# Guitutar_LEDS.net
KiCad netlist of a schematic drawn in EAGLE
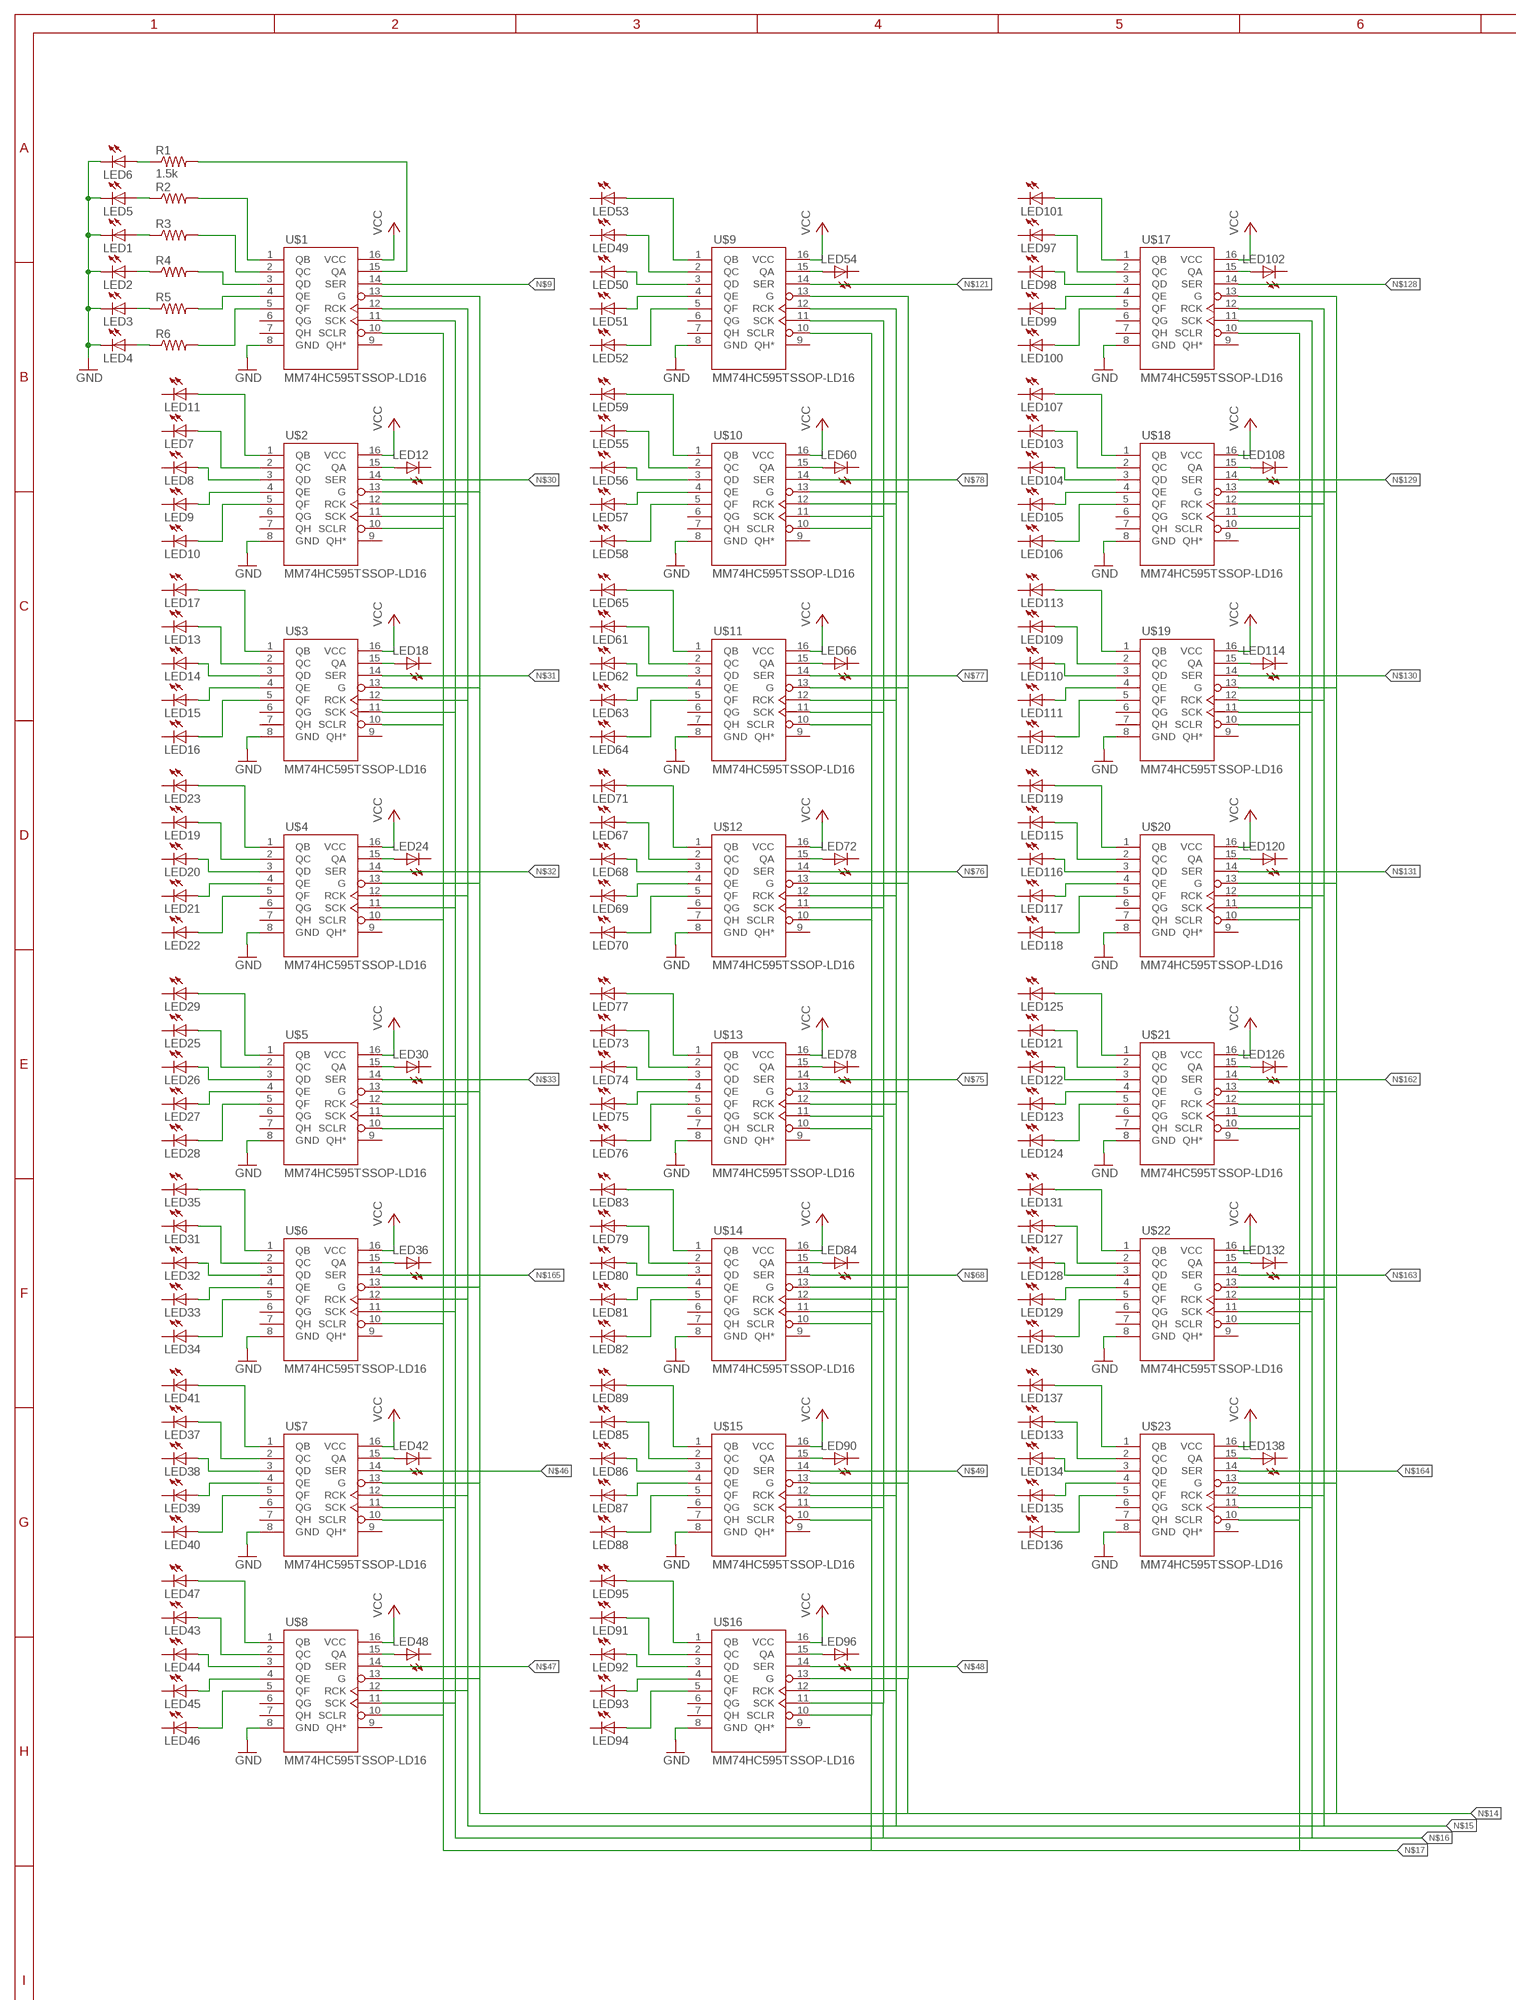
[diagram p0: schematic, sheet 1, part 1 of 2]
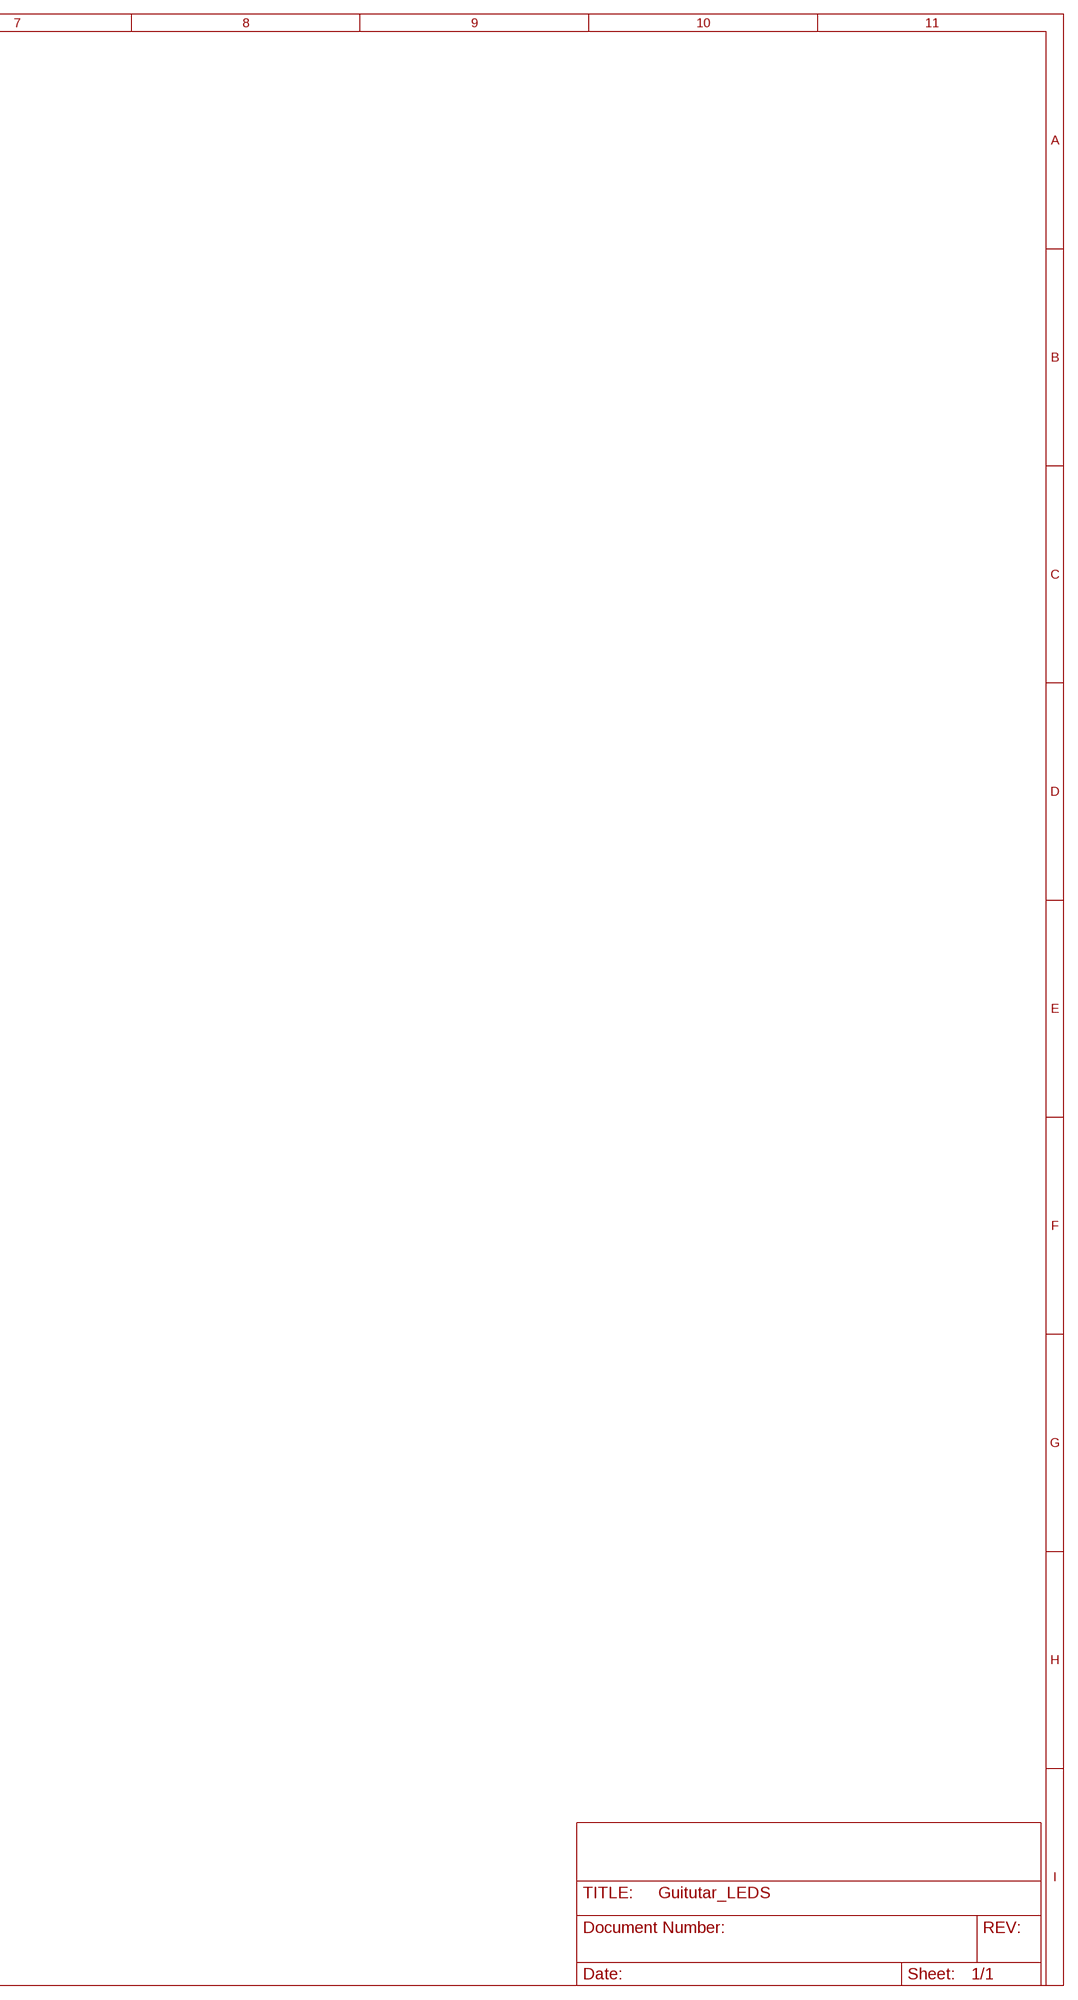
[diagram p1: schematic, sheet 1, part 2 of 2]

(export (version "E")
  (design (tool "Eeschema 10.0.6"))
  (components
    (comp (ref "LED1")
      (value "LEDSMT1206")
      (footprint "eagle-import:1206")
      (libsource (lib "eagle-import") (part "LEDSMT1206"))
    )
    (comp (ref "LED2")
      (value "LEDSMT1206")
      (footprint "eagle-import:1206")
      (libsource (lib "eagle-import") (part "LEDSMT1206"))
    )
    (comp (ref "LED3")
      (value "LEDSMT1206")
      (footprint "eagle-import:1206")
      (libsource (lib "eagle-import") (part "LEDSMT1206"))
    )
    (comp (ref "LED4")
      (value "LEDSMT1206")
      (footprint "eagle-import:1206")
      (libsource (lib "eagle-import") (part "LEDSMT1206"))
    )
    (comp (ref "LED5")
      (value "LEDSMT1206")
      (footprint "eagle-import:1206")
      (libsource (lib "eagle-import") (part "LEDSMT1206"))
    )
    (comp (ref "LED6")
      (value "LEDSMT1206")
      (footprint "eagle-import:1206")
      (libsource (lib "eagle-import") (part "LEDSMT1206"))
    )
    (comp (ref "LED7")
      (value "LEDSMT1206")
      (footprint "eagle-import:1206")
      (libsource (lib "eagle-import") (part "LEDSMT1206"))
    )
    (comp (ref "LED8")
      (value "LEDSMT1206")
      (footprint "eagle-import:1206")
      (libsource (lib "eagle-import") (part "LEDSMT1206"))
    )
    (comp (ref "LED9")
      (value "LEDSMT1206")
      (footprint "eagle-import:1206")
      (libsource (lib "eagle-import") (part "LEDSMT1206"))
    )
    (comp (ref "LED10")
      (value "LEDSMT1206")
      (footprint "eagle-import:1206")
      (libsource (lib "eagle-import") (part "LEDSMT1206"))
    )
    (comp (ref "LED11")
      (value "LEDSMT1206")
      (footprint "eagle-import:1206")
      (libsource (lib "eagle-import") (part "LEDSMT1206"))
    )
    (comp (ref "LED12")
      (value "LEDSMT1206")
      (footprint "eagle-import:1206")
      (libsource (lib "eagle-import") (part "LEDSMT1206"))
    )
    (comp (ref "LED13")
      (value "LEDSMT1206")
      (footprint "eagle-import:1206")
      (libsource (lib "eagle-import") (part "LEDSMT1206"))
    )
    (comp (ref "LED14")
      (value "LEDSMT1206")
      (footprint "eagle-import:1206")
      (libsource (lib "eagle-import") (part "LEDSMT1206"))
    )
    (comp (ref "LED15")
      (value "LEDSMT1206")
      (footprint "eagle-import:1206")
      (libsource (lib "eagle-import") (part "LEDSMT1206"))
    )
    (comp (ref "LED16")
      (value "LEDSMT1206")
      (footprint "eagle-import:1206")
      (libsource (lib "eagle-import") (part "LEDSMT1206"))
    )
    (comp (ref "LED17")
      (value "LEDSMT1206")
      (footprint "eagle-import:1206")
      (libsource (lib "eagle-import") (part "LEDSMT1206"))
    )
    (comp (ref "LED18")
      (value "LEDSMT1206")
      (footprint "eagle-import:1206")
      (libsource (lib "eagle-import") (part "LEDSMT1206"))
    )
    (comp (ref "LED19")
      (value "LEDSMT1206")
      (footprint "eagle-import:1206")
      (libsource (lib "eagle-import") (part "LEDSMT1206"))
    )
    (comp (ref "LED20")
      (value "LEDSMT1206")
      (footprint "eagle-import:1206")
      (libsource (lib "eagle-import") (part "LEDSMT1206"))
    )
    (comp (ref "LED21")
      (value "LEDSMT1206")
      (footprint "eagle-import:1206")
      (libsource (lib "eagle-import") (part "LEDSMT1206"))
    )
    (comp (ref "LED22")
      (value "LEDSMT1206")
      (footprint "eagle-import:1206")
      (libsource (lib "eagle-import") (part "LEDSMT1206"))
    )
    (comp (ref "LED23")
      (value "LEDSMT1206")
      (footprint "eagle-import:1206")
      (libsource (lib "eagle-import") (part "LEDSMT1206"))
    )
    (comp (ref "LED24")
      (value "LEDSMT1206")
      (footprint "eagle-import:1206")
      (libsource (lib "eagle-import") (part "LEDSMT1206"))
    )
    (comp (ref "LED25")
      (value "LEDSMT1206")
      (footprint "eagle-import:1206")
      (libsource (lib "eagle-import") (part "LEDSMT1206"))
    )
    (comp (ref "LED26")
      (value "LEDSMT1206")
      (footprint "eagle-import:1206")
      (libsource (lib "eagle-import") (part "LEDSMT1206"))
    )
    (comp (ref "LED27")
      (value "LEDSMT1206")
      (footprint "eagle-import:1206")
      (libsource (lib "eagle-import") (part "LEDSMT1206"))
    )
    (comp (ref "LED28")
      (value "LEDSMT1206")
      (footprint "eagle-import:1206")
      (libsource (lib "eagle-import") (part "LEDSMT1206"))
    )
    (comp (ref "LED29")
      (value "LEDSMT1206")
      (footprint "eagle-import:1206")
      (libsource (lib "eagle-import") (part "LEDSMT1206"))
    )
    (comp (ref "LED30")
      (value "LEDSMT1206")
      (footprint "eagle-import:1206")
      (libsource (lib "eagle-import") (part "LEDSMT1206"))
    )
    (comp (ref "LED31")
      (value "LEDSMT1206")
      (footprint "eagle-import:1206")
      (libsource (lib "eagle-import") (part "LEDSMT1206"))
    )
    (comp (ref "LED32")
      (value "LEDSMT1206")
      (footprint "eagle-import:1206")
      (libsource (lib "eagle-import") (part "LEDSMT1206"))
    )
    (comp (ref "LED33")
      (value "LEDSMT1206")
      (footprint "eagle-import:1206")
      (libsource (lib "eagle-import") (part "LEDSMT1206"))
    )
    (comp (ref "LED34")
      (value "LEDSMT1206")
      (footprint "eagle-import:1206")
      (libsource (lib "eagle-import") (part "LEDSMT1206"))
    )
    (comp (ref "LED35")
      (value "LEDSMT1206")
      (footprint "eagle-import:1206")
      (libsource (lib "eagle-import") (part "LEDSMT1206"))
    )
    (comp (ref "LED36")
      (value "LEDSMT1206")
      (footprint "eagle-import:1206")
      (libsource (lib "eagle-import") (part "LEDSMT1206"))
    )
    (comp (ref "LED37")
      (value "LEDSMT1206")
      (footprint "eagle-import:1206")
      (libsource (lib "eagle-import") (part "LEDSMT1206"))
    )
    (comp (ref "LED38")
      (value "LEDSMT1206")
      (footprint "eagle-import:1206")
      (libsource (lib "eagle-import") (part "LEDSMT1206"))
    )
    (comp (ref "LED39")
      (value "LEDSMT1206")
      (footprint "eagle-import:1206")
      (libsource (lib "eagle-import") (part "LEDSMT1206"))
    )
    (comp (ref "LED40")
      (value "LEDSMT1206")
      (footprint "eagle-import:1206")
      (libsource (lib "eagle-import") (part "LEDSMT1206"))
    )
    (comp (ref "LED41")
      (value "LEDSMT1206")
      (footprint "eagle-import:1206")
      (libsource (lib "eagle-import") (part "LEDSMT1206"))
    )
    (comp (ref "LED42")
      (value "LEDSMT1206")
      (footprint "eagle-import:1206")
      (libsource (lib "eagle-import") (part "LEDSMT1206"))
    )
    (comp (ref "LED43")
      (value "LEDSMT1206")
      (footprint "eagle-import:1206")
      (libsource (lib "eagle-import") (part "LEDSMT1206"))
    )
    (comp (ref "LED44")
      (value "LEDSMT1206")
      (footprint "eagle-import:1206")
      (libsource (lib "eagle-import") (part "LEDSMT1206"))
    )
    (comp (ref "LED45")
      (value "LEDSMT1206")
      (footprint "eagle-import:1206")
      (libsource (lib "eagle-import") (part "LEDSMT1206"))
    )
    (comp (ref "LED46")
      (value "LEDSMT1206")
      (footprint "eagle-import:1206")
      (libsource (lib "eagle-import") (part "LEDSMT1206"))
    )
    (comp (ref "LED47")
      (value "LEDSMT1206")
      (footprint "eagle-import:1206")
      (libsource (lib "eagle-import") (part "LEDSMT1206"))
    )
    (comp (ref "LED48")
      (value "LEDSMT1206")
      (footprint "eagle-import:1206")
      (libsource (lib "eagle-import") (part "LEDSMT1206"))
    )
    (comp (ref "LED49")
      (value "LEDSMT1206")
      (footprint "eagle-import:1206")
      (libsource (lib "eagle-import") (part "LEDSMT1206"))
    )
    (comp (ref "LED50")
      (value "LEDSMT1206")
      (footprint "eagle-import:1206")
      (libsource (lib "eagle-import") (part "LEDSMT1206"))
    )
    (comp (ref "LED51")
      (value "LEDSMT1206")
      (footprint "eagle-import:1206")
      (libsource (lib "eagle-import") (part "LEDSMT1206"))
    )
    (comp (ref "LED52")
      (value "LEDSMT1206")
      (footprint "eagle-import:1206")
      (libsource (lib "eagle-import") (part "LEDSMT1206"))
    )
    (comp (ref "LED53")
      (value "LEDSMT1206")
      (footprint "eagle-import:1206")
      (libsource (lib "eagle-import") (part "LEDSMT1206"))
    )
    (comp (ref "LED54")
      (value "LEDSMT1206")
      (footprint "eagle-import:1206")
      (libsource (lib "eagle-import") (part "LEDSMT1206"))
    )
    (comp (ref "LED55")
      (value "LEDSMT1206")
      (footprint "eagle-import:1206")
      (libsource (lib "eagle-import") (part "LEDSMT1206"))
    )
    (comp (ref "LED56")
      (value "LEDSMT1206")
      (footprint "eagle-import:1206")
      (libsource (lib "eagle-import") (part "LEDSMT1206"))
    )
    (comp (ref "LED57")
      (value "LEDSMT1206")
      (footprint "eagle-import:1206")
      (libsource (lib "eagle-import") (part "LEDSMT1206"))
    )
    (comp (ref "LED58")
      (value "LEDSMT1206")
      (footprint "eagle-import:1206")
      (libsource (lib "eagle-import") (part "LEDSMT1206"))
    )
    (comp (ref "LED59")
      (value "LEDSMT1206")
      (footprint "eagle-import:1206")
      (libsource (lib "eagle-import") (part "LEDSMT1206"))
    )
    (comp (ref "LED60")
      (value "LEDSMT1206")
      (footprint "eagle-import:1206")
      (libsource (lib "eagle-import") (part "LEDSMT1206"))
    )
    (comp (ref "LED61")
      (value "LEDSMT1206")
      (footprint "eagle-import:1206")
      (libsource (lib "eagle-import") (part "LEDSMT1206"))
    )
    (comp (ref "LED62")
      (value "LEDSMT1206")
      (footprint "eagle-import:1206")
      (libsource (lib "eagle-import") (part "LEDSMT1206"))
    )
    (comp (ref "LED63")
      (value "LEDSMT1206")
      (footprint "eagle-import:1206")
      (libsource (lib "eagle-import") (part "LEDSMT1206"))
    )
    (comp (ref "LED64")
      (value "LEDSMT1206")
      (footprint "eagle-import:1206")
      (libsource (lib "eagle-import") (part "LEDSMT1206"))
    )
    (comp (ref "LED65")
      (value "LEDSMT1206")
      (footprint "eagle-import:1206")
      (libsource (lib "eagle-import") (part "LEDSMT1206"))
    )
    (comp (ref "LED66")
      (value "LEDSMT1206")
      (footprint "eagle-import:1206")
      (libsource (lib "eagle-import") (part "LEDSMT1206"))
    )
    (comp (ref "LED67")
      (value "LEDSMT1206")
      (footprint "eagle-import:1206")
      (libsource (lib "eagle-import") (part "LEDSMT1206"))
    )
    (comp (ref "LED68")
      (value "LEDSMT1206")
      (footprint "eagle-import:1206")
      (libsource (lib "eagle-import") (part "LEDSMT1206"))
    )
    (comp (ref "LED69")
      (value "LEDSMT1206")
      (footprint "eagle-import:1206")
      (libsource (lib "eagle-import") (part "LEDSMT1206"))
    )
    (comp (ref "LED70")
      (value "LEDSMT1206")
      (footprint "eagle-import:1206")
      (libsource (lib "eagle-import") (part "LEDSMT1206"))
    )
    (comp (ref "LED71")
      (value "LEDSMT1206")
      (footprint "eagle-import:1206")
      (libsource (lib "eagle-import") (part "LEDSMT1206"))
    )
    (comp (ref "LED72")
      (value "LEDSMT1206")
      (footprint "eagle-import:1206")
      (libsource (lib "eagle-import") (part "LEDSMT1206"))
    )
    (comp (ref "LED73")
      (value "LEDSMT1206")
      (footprint "eagle-import:1206")
      (libsource (lib "eagle-import") (part "LEDSMT1206"))
    )
    (comp (ref "LED74")
      (value "LEDSMT1206")
      (footprint "eagle-import:1206")
      (libsource (lib "eagle-import") (part "LEDSMT1206"))
    )
    (comp (ref "LED75")
      (value "LEDSMT1206")
      (footprint "eagle-import:1206")
      (libsource (lib "eagle-import") (part "LEDSMT1206"))
    )
    (comp (ref "LED76")
      (value "LEDSMT1206")
      (footprint "eagle-import:1206")
      (libsource (lib "eagle-import") (part "LEDSMT1206"))
    )
    (comp (ref "LED77")
      (value "LEDSMT1206")
      (footprint "eagle-import:1206")
      (libsource (lib "eagle-import") (part "LEDSMT1206"))
    )
    (comp (ref "LED78")
      (value "LEDSMT1206")
      (footprint "eagle-import:1206")
      (libsource (lib "eagle-import") (part "LEDSMT1206"))
    )
    (comp (ref "LED79")
      (value "LEDSMT1206")
      (footprint "eagle-import:1206")
      (libsource (lib "eagle-import") (part "LEDSMT1206"))
    )
    (comp (ref "LED80")
      (value "LEDSMT1206")
      (footprint "eagle-import:1206")
      (libsource (lib "eagle-import") (part "LEDSMT1206"))
    )
    (comp (ref "LED81")
      (value "LEDSMT1206")
      (footprint "eagle-import:1206")
      (libsource (lib "eagle-import") (part "LEDSMT1206"))
    )
    (comp (ref "LED82")
      (value "LEDSMT1206")
      (footprint "eagle-import:1206")
      (libsource (lib "eagle-import") (part "LEDSMT1206"))
    )
    (comp (ref "LED83")
      (value "LEDSMT1206")
      (footprint "eagle-import:1206")
      (libsource (lib "eagle-import") (part "LEDSMT1206"))
    )
    (comp (ref "LED84")
      (value "LEDSMT1206")
      (footprint "eagle-import:1206")
      (libsource (lib "eagle-import") (part "LEDSMT1206"))
    )
    (comp (ref "LED85")
      (value "LEDSMT1206")
      (footprint "eagle-import:1206")
      (libsource (lib "eagle-import") (part "LEDSMT1206"))
    )
    (comp (ref "LED86")
      (value "LEDSMT1206")
      (footprint "eagle-import:1206")
      (libsource (lib "eagle-import") (part "LEDSMT1206"))
    )
    (comp (ref "LED87")
      (value "LEDSMT1206")
      (footprint "eagle-import:1206")
      (libsource (lib "eagle-import") (part "LEDSMT1206"))
    )
    (comp (ref "LED88")
      (value "LEDSMT1206")
      (footprint "eagle-import:1206")
      (libsource (lib "eagle-import") (part "LEDSMT1206"))
    )
    (comp (ref "LED89")
      (value "LEDSMT1206")
      (footprint "eagle-import:1206")
      (libsource (lib "eagle-import") (part "LEDSMT1206"))
    )
    (comp (ref "LED90")
      (value "LEDSMT1206")
      (footprint "eagle-import:1206")
      (libsource (lib "eagle-import") (part "LEDSMT1206"))
    )
    (comp (ref "LED91")
      (value "LEDSMT1206")
      (footprint "eagle-import:1206")
      (libsource (lib "eagle-import") (part "LEDSMT1206"))
    )
    (comp (ref "LED92")
      (value "LEDSMT1206")
      (footprint "eagle-import:1206")
      (libsource (lib "eagle-import") (part "LEDSMT1206"))
    )
    (comp (ref "LED93")
      (value "LEDSMT1206")
      (footprint "eagle-import:1206")
      (libsource (lib "eagle-import") (part "LEDSMT1206"))
    )
    (comp (ref "LED94")
      (value "LEDSMT1206")
      (footprint "eagle-import:1206")
      (libsource (lib "eagle-import") (part "LEDSMT1206"))
    )
    (comp (ref "LED95")
      (value "LEDSMT1206")
      (footprint "eagle-import:1206")
      (libsource (lib "eagle-import") (part "LEDSMT1206"))
    )
    (comp (ref "LED96")
      (value "LEDSMT1206")
      (footprint "eagle-import:1206")
      (libsource (lib "eagle-import") (part "LEDSMT1206"))
    )
    (comp (ref "LED97")
      (value "LEDSMT1206")
      (footprint "eagle-import:1206")
      (libsource (lib "eagle-import") (part "LEDSMT1206"))
    )
    (comp (ref "LED98")
      (value "LEDSMT1206")
      (footprint "eagle-import:1206")
      (libsource (lib "eagle-import") (part "LEDSMT1206"))
    )
    (comp (ref "LED99")
      (value "LEDSMT1206")
      (footprint "eagle-import:1206")
      (libsource (lib "eagle-import") (part "LEDSMT1206"))
    )
    (comp (ref "LED100")
      (value "LEDSMT1206")
      (footprint "eagle-import:1206")
      (libsource (lib "eagle-import") (part "LEDSMT1206"))
    )
    (comp (ref "LED101")
      (value "LEDSMT1206")
      (footprint "eagle-import:1206")
      (libsource (lib "eagle-import") (part "LEDSMT1206"))
    )
    (comp (ref "LED102")
      (value "LEDSMT1206")
      (footprint "eagle-import:1206")
      (libsource (lib "eagle-import") (part "LEDSMT1206"))
    )
    (comp (ref "LED103")
      (value "LEDSMT1206")
      (footprint "eagle-import:1206")
      (libsource (lib "eagle-import") (part "LEDSMT1206"))
    )
    (comp (ref "LED104")
      (value "LEDSMT1206")
      (footprint "eagle-import:1206")
      (libsource (lib "eagle-import") (part "LEDSMT1206"))
    )
    (comp (ref "LED105")
      (value "LEDSMT1206")
      (footprint "eagle-import:1206")
      (libsource (lib "eagle-import") (part "LEDSMT1206"))
    )
    (comp (ref "LED106")
      (value "LEDSMT1206")
      (footprint "eagle-import:1206")
      (libsource (lib "eagle-import") (part "LEDSMT1206"))
    )
    (comp (ref "LED107")
      (value "LEDSMT1206")
      (footprint "eagle-import:1206")
      (libsource (lib "eagle-import") (part "LEDSMT1206"))
    )
    (comp (ref "LED108")
      (value "LEDSMT1206")
      (footprint "eagle-import:1206")
      (libsource (lib "eagle-import") (part "LEDSMT1206"))
    )
    (comp (ref "LED109")
      (value "LEDSMT1206")
      (footprint "eagle-import:1206")
      (libsource (lib "eagle-import") (part "LEDSMT1206"))
    )
    (comp (ref "LED110")
      (value "LEDSMT1206")
      (footprint "eagle-import:1206")
      (libsource (lib "eagle-import") (part "LEDSMT1206"))
    )
    (comp (ref "LED111")
      (value "LEDSMT1206")
      (footprint "eagle-import:1206")
      (libsource (lib "eagle-import") (part "LEDSMT1206"))
    )
    (comp (ref "LED112")
      (value "LEDSMT1206")
      (footprint "eagle-import:1206")
      (libsource (lib "eagle-import") (part "LEDSMT1206"))
    )
    (comp (ref "LED113")
      (value "LEDSMT1206")
      (footprint "eagle-import:1206")
      (libsource (lib "eagle-import") (part "LEDSMT1206"))
    )
    (comp (ref "LED114")
      (value "LEDSMT1206")
      (footprint "eagle-import:1206")
      (libsource (lib "eagle-import") (part "LEDSMT1206"))
    )
    (comp (ref "LED115")
      (value "LEDSMT1206")
      (footprint "eagle-import:1206")
      (libsource (lib "eagle-import") (part "LEDSMT1206"))
    )
    (comp (ref "LED116")
      (value "LEDSMT1206")
      (footprint "eagle-import:1206")
      (libsource (lib "eagle-import") (part "LEDSMT1206"))
    )
    (comp (ref "LED117")
      (value "LEDSMT1206")
      (footprint "eagle-import:1206")
      (libsource (lib "eagle-import") (part "LEDSMT1206"))
    )
    (comp (ref "LED118")
      (value "LEDSMT1206")
      (footprint "eagle-import:1206")
      (libsource (lib "eagle-import") (part "LEDSMT1206"))
    )
    (comp (ref "LED119")
      (value "LEDSMT1206")
      (footprint "eagle-import:1206")
      (libsource (lib "eagle-import") (part "LEDSMT1206"))
    )
    (comp (ref "LED120")
      (value "LEDSMT1206")
      (footprint "eagle-import:1206")
      (libsource (lib "eagle-import") (part "LEDSMT1206"))
    )
    (comp (ref "LED121")
      (value "LEDSMT1206")
      (footprint "eagle-import:1206")
      (libsource (lib "eagle-import") (part "LEDSMT1206"))
    )
    (comp (ref "LED122")
      (value "LEDSMT1206")
      (footprint "eagle-import:1206")
      (libsource (lib "eagle-import") (part "LEDSMT1206"))
    )
    (comp (ref "LED123")
      (value "LEDSMT1206")
      (footprint "eagle-import:1206")
      (libsource (lib "eagle-import") (part "LEDSMT1206"))
    )
    (comp (ref "LED124")
      (value "LEDSMT1206")
      (footprint "eagle-import:1206")
      (libsource (lib "eagle-import") (part "LEDSMT1206"))
    )
    (comp (ref "LED125")
      (value "LEDSMT1206")
      (footprint "eagle-import:1206")
      (libsource (lib "eagle-import") (part "LEDSMT1206"))
    )
    (comp (ref "LED126")
      (value "LEDSMT1206")
      (footprint "eagle-import:1206")
      (libsource (lib "eagle-import") (part "LEDSMT1206"))
    )
    (comp (ref "LED127")
      (value "LEDSMT1206")
      (footprint "eagle-import:1206")
      (libsource (lib "eagle-import") (part "LEDSMT1206"))
    )
    (comp (ref "LED128")
      (value "LEDSMT1206")
      (footprint "eagle-import:1206")
      (libsource (lib "eagle-import") (part "LEDSMT1206"))
    )
    (comp (ref "LED129")
      (value "LEDSMT1206")
      (footprint "eagle-import:1206")
      (libsource (lib "eagle-import") (part "LEDSMT1206"))
    )
    (comp (ref "LED130")
      (value "LEDSMT1206")
      (footprint "eagle-import:1206")
      (libsource (lib "eagle-import") (part "LEDSMT1206"))
    )
    (comp (ref "LED131")
      (value "LEDSMT1206")
      (footprint "eagle-import:1206")
      (libsource (lib "eagle-import") (part "LEDSMT1206"))
    )
    (comp (ref "LED132")
      (value "LEDSMT1206")
      (footprint "eagle-import:1206")
      (libsource (lib "eagle-import") (part "LEDSMT1206"))
    )
    (comp (ref "LED133")
      (value "LEDSMT1206")
      (footprint "eagle-import:1206")
      (libsource (lib "eagle-import") (part "LEDSMT1206"))
    )
    (comp (ref "LED134")
      (value "LEDSMT1206")
      (footprint "eagle-import:1206")
      (libsource (lib "eagle-import") (part "LEDSMT1206"))
    )
    (comp (ref "LED135")
      (value "LEDSMT1206")
      (footprint "eagle-import:1206")
      (libsource (lib "eagle-import") (part "LEDSMT1206"))
    )
    (comp (ref "LED136")
      (value "LEDSMT1206")
      (footprint "eagle-import:1206")
      (libsource (lib "eagle-import") (part "LEDSMT1206"))
    )
    (comp (ref "LED137")
      (value "LEDSMT1206")
      (footprint "eagle-import:1206")
      (libsource (lib "eagle-import") (part "LEDSMT1206"))
    )
    (comp (ref "LED138")
      (value "LEDSMT1206")
      (footprint "eagle-import:1206")
      (libsource (lib "eagle-import") (part "LEDSMT1206"))
    )
    (comp (ref "R1")
      (value "1.5k")
      (footprint "eagle-import:R0603")
      (libsource (lib "eagle-import") (part "R-US_R0603"))
    )
    (comp (ref "R2")
      (value "R-US_R0603")
      (footprint "eagle-import:R0603")
      (libsource (lib "eagle-import") (part "R-US_R0603"))
    )
    (comp (ref "R3")
      (value "R-US_R0603")
      (footprint "eagle-import:R0603")
      (libsource (lib "eagle-import") (part "R-US_R0603"))
    )
    (comp (ref "R4")
      (value "R-US_R0603")
      (footprint "eagle-import:R0603")
      (libsource (lib "eagle-import") (part "R-US_R0603"))
    )
    (comp (ref "R5")
      (value "R-US_R0603")
      (footprint "eagle-import:R0603")
      (libsource (lib "eagle-import") (part "R-US_R0603"))
    )
    (comp (ref "R6")
      (value "R-US_R0603")
      (footprint "eagle-import:R0603")
      (libsource (lib "eagle-import") (part "R-US_R0603"))
    )
    (comp (ref "U$1")
      (value "MM74HC595TSSOP-LD16")
      (footprint "eagle-import:MM74HC595MTCXCT-ND")
      (libsource (lib "eagle-import") (part "MM74HC595TSSOP-LD16"))
    )
    (comp (ref "U$2")
      (value "MM74HC595TSSOP-LD16")
      (footprint "eagle-import:MM74HC595MTCXCT-ND")
      (libsource (lib "eagle-import") (part "MM74HC595TSSOP-LD16"))
    )
    (comp (ref "U$3")
      (value "MM74HC595TSSOP-LD16")
      (footprint "eagle-import:MM74HC595MTCXCT-ND")
      (libsource (lib "eagle-import") (part "MM74HC595TSSOP-LD16"))
    )
    (comp (ref "U$4")
      (value "MM74HC595TSSOP-LD16")
      (footprint "eagle-import:MM74HC595MTCXCT-ND")
      (libsource (lib "eagle-import") (part "MM74HC595TSSOP-LD16"))
    )
    (comp (ref "U$5")
      (value "MM74HC595TSSOP-LD16")
      (footprint "eagle-import:MM74HC595MTCXCT-ND")
      (libsource (lib "eagle-import") (part "MM74HC595TSSOP-LD16"))
    )
    (comp (ref "U$6")
      (value "MM74HC595TSSOP-LD16")
      (footprint "eagle-import:MM74HC595MTCXCT-ND")
      (libsource (lib "eagle-import") (part "MM74HC595TSSOP-LD16"))
    )
    (comp (ref "U$7")
      (value "MM74HC595TSSOP-LD16")
      (footprint "eagle-import:MM74HC595MTCXCT-ND")
      (libsource (lib "eagle-import") (part "MM74HC595TSSOP-LD16"))
    )
    (comp (ref "U$8")
      (value "MM74HC595TSSOP-LD16")
      (footprint "eagle-import:MM74HC595MTCXCT-ND")
      (libsource (lib "eagle-import") (part "MM74HC595TSSOP-LD16"))
    )
    (comp (ref "U$9")
      (value "MM74HC595TSSOP-LD16")
      (footprint "eagle-import:MM74HC595MTCXCT-ND")
      (libsource (lib "eagle-import") (part "MM74HC595TSSOP-LD16"))
    )
    (comp (ref "U$10")
      (value "MM74HC595TSSOP-LD16")
      (footprint "eagle-import:MM74HC595MTCXCT-ND")
      (libsource (lib "eagle-import") (part "MM74HC595TSSOP-LD16"))
    )
    (comp (ref "U$11")
      (value "MM74HC595TSSOP-LD16")
      (footprint "eagle-import:MM74HC595MTCXCT-ND")
      (libsource (lib "eagle-import") (part "MM74HC595TSSOP-LD16"))
    )
    (comp (ref "U$12")
      (value "MM74HC595TSSOP-LD16")
      (footprint "eagle-import:MM74HC595MTCXCT-ND")
      (libsource (lib "eagle-import") (part "MM74HC595TSSOP-LD16"))
    )
    (comp (ref "U$13")
      (value "MM74HC595TSSOP-LD16")
      (footprint "eagle-import:MM74HC595MTCXCT-ND")
      (libsource (lib "eagle-import") (part "MM74HC595TSSOP-LD16"))
    )
    (comp (ref "U$14")
      (value "MM74HC595TSSOP-LD16")
      (footprint "eagle-import:MM74HC595MTCXCT-ND")
      (libsource (lib "eagle-import") (part "MM74HC595TSSOP-LD16"))
    )
    (comp (ref "U$15")
      (value "MM74HC595TSSOP-LD16")
      (footprint "eagle-import:MM74HC595MTCXCT-ND")
      (libsource (lib "eagle-import") (part "MM74HC595TSSOP-LD16"))
    )
    (comp (ref "U$16")
      (value "MM74HC595TSSOP-LD16")
      (footprint "eagle-import:MM74HC595MTCXCT-ND")
      (libsource (lib "eagle-import") (part "MM74HC595TSSOP-LD16"))
    )
    (comp (ref "U$17")
      (value "MM74HC595TSSOP-LD16")
      (footprint "eagle-import:MM74HC595MTCXCT-ND")
      (libsource (lib "eagle-import") (part "MM74HC595TSSOP-LD16"))
    )
    (comp (ref "U$18")
      (value "MM74HC595TSSOP-LD16")
      (footprint "eagle-import:MM74HC595MTCXCT-ND")
      (libsource (lib "eagle-import") (part "MM74HC595TSSOP-LD16"))
    )
    (comp (ref "U$19")
      (value "MM74HC595TSSOP-LD16")
      (footprint "eagle-import:MM74HC595MTCXCT-ND")
      (libsource (lib "eagle-import") (part "MM74HC595TSSOP-LD16"))
    )
    (comp (ref "U$20")
      (value "MM74HC595TSSOP-LD16")
      (footprint "eagle-import:MM74HC595MTCXCT-ND")
      (libsource (lib "eagle-import") (part "MM74HC595TSSOP-LD16"))
    )
    (comp (ref "U$21")
      (value "MM74HC595TSSOP-LD16")
      (footprint "eagle-import:MM74HC595MTCXCT-ND")
      (libsource (lib "eagle-import") (part "MM74HC595TSSOP-LD16"))
    )
    (comp (ref "U$22")
      (value "MM74HC595TSSOP-LD16")
      (footprint "eagle-import:MM74HC595MTCXCT-ND")
      (libsource (lib "eagle-import") (part "MM74HC595TSSOP-LD16"))
    )
    (comp (ref "U$23")
      (value "MM74HC595TSSOP-LD16")
      (footprint "eagle-import:MM74HC595MTCXCT-ND")
      (libsource (lib "eagle-import") (part "MM74HC595TSSOP-LD16"))
    )
  )
  (nets
    (net (code "1") (name "GND") (class "Default")
      (node (ref "LED1") (pin "C") (pinfunction "C_C") (pintype "passive"))
      (node (ref "LED2") (pin "C") (pinfunction "C_C") (pintype "passive"))
      (node (ref "LED3") (pin "C") (pinfunction "C_C") (pintype "passive"))
      (node (ref "LED4") (pin "C") (pinfunction "C_C") (pintype "passive"))
      (node (ref "LED5") (pin "C") (pinfunction "C_C") (pintype "passive"))
      (node (ref "LED6") (pin "C") (pinfunction "C_C") (pintype "passive"))
      (node (ref "U$1") (pin "8") (pinfunction "GND_8") (pintype "bidirectional"))
      (node (ref "U$10") (pin "8") (pinfunction "GND_8") (pintype "bidirectional"))
      (node (ref "U$11") (pin "8") (pinfunction "GND_8") (pintype "bidirectional"))
      (node (ref "U$12") (pin "8") (pinfunction "GND_8") (pintype "bidirectional"))
      (node (ref "U$13") (pin "8") (pinfunction "GND_8") (pintype "bidirectional"))
      (node (ref "U$14") (pin "8") (pinfunction "GND_8") (pintype "bidirectional"))
      (node (ref "U$15") (pin "8") (pinfunction "GND_8") (pintype "bidirectional"))
      (node (ref "U$16") (pin "8") (pinfunction "GND_8") (pintype "bidirectional"))
      (node (ref "U$17") (pin "8") (pinfunction "GND_8") (pintype "bidirectional"))
      (node (ref "U$18") (pin "8") (pinfunction "GND_8") (pintype "bidirectional"))
      (node (ref "U$19") (pin "8") (pinfunction "GND_8") (pintype "bidirectional"))
      (node (ref "U$2") (pin "8") (pinfunction "GND_8") (pintype "bidirectional"))
      (node (ref "U$20") (pin "8") (pinfunction "GND_8") (pintype "bidirectional"))
      (node (ref "U$21") (pin "8") (pinfunction "GND_8") (pintype "bidirectional"))
      (node (ref "U$22") (pin "8") (pinfunction "GND_8") (pintype "bidirectional"))
      (node (ref "U$23") (pin "8") (pinfunction "GND_8") (pintype "bidirectional"))
      (node (ref "U$3") (pin "8") (pinfunction "GND_8") (pintype "bidirectional"))
      (node (ref "U$4") (pin "8") (pinfunction "GND_8") (pintype "bidirectional"))
      (node (ref "U$5") (pin "8") (pinfunction "GND_8") (pintype "bidirectional"))
      (node (ref "U$6") (pin "8") (pinfunction "GND_8") (pintype "bidirectional"))
      (node (ref "U$7") (pin "8") (pinfunction "GND_8") (pintype "bidirectional"))
      (node (ref "U$8") (pin "8") (pinfunction "GND_8") (pintype "bidirectional"))
      (node (ref "U$9") (pin "8") (pinfunction "GND_8") (pintype "bidirectional"))
    )
    (net (code "2") (name "N$9") (class "Default")
      (node (ref "U$1") (pin "14") (pinfunction "SER_14") (pintype "bidirectional"))
    )
    (net (code "3") (name "N$14") (class "Default")
      (node (ref "U$1") (pin "13") (pinfunction "G_13") (pintype "bidirectional"))
      (node (ref "U$10") (pin "13") (pinfunction "G_13") (pintype "bidirectional"))
      (node (ref "U$11") (pin "13") (pinfunction "G_13") (pintype "bidirectional"))
      (node (ref "U$12") (pin "13") (pinfunction "G_13") (pintype "bidirectional"))
      (node (ref "U$13") (pin "13") (pinfunction "G_13") (pintype "bidirectional"))
      (node (ref "U$14") (pin "13") (pinfunction "G_13") (pintype "bidirectional"))
      (node (ref "U$15") (pin "13") (pinfunction "G_13") (pintype "bidirectional"))
      (node (ref "U$16") (pin "13") (pinfunction "G_13") (pintype "bidirectional"))
      (node (ref "U$17") (pin "13") (pinfunction "G_13") (pintype "bidirectional"))
      (node (ref "U$18") (pin "13") (pinfunction "G_13") (pintype "bidirectional"))
      (node (ref "U$19") (pin "13") (pinfunction "G_13") (pintype "bidirectional"))
      (node (ref "U$2") (pin "13") (pinfunction "G_13") (pintype "bidirectional"))
      (node (ref "U$20") (pin "13") (pinfunction "G_13") (pintype "bidirectional"))
      (node (ref "U$21") (pin "13") (pinfunction "G_13") (pintype "bidirectional"))
      (node (ref "U$22") (pin "13") (pinfunction "G_13") (pintype "bidirectional"))
      (node (ref "U$23") (pin "13") (pinfunction "G_13") (pintype "bidirectional"))
      (node (ref "U$3") (pin "13") (pinfunction "G_13") (pintype "bidirectional"))
      (node (ref "U$4") (pin "13") (pinfunction "G_13") (pintype "bidirectional"))
      (node (ref "U$5") (pin "13") (pinfunction "G_13") (pintype "bidirectional"))
      (node (ref "U$6") (pin "13") (pinfunction "G_13") (pintype "bidirectional"))
      (node (ref "U$7") (pin "13") (pinfunction "G_13") (pintype "bidirectional"))
      (node (ref "U$8") (pin "13") (pinfunction "G_13") (pintype "bidirectional"))
      (node (ref "U$9") (pin "13") (pinfunction "G_13") (pintype "bidirectional"))
    )
    (net (code "4") (name "N$15") (class "Default")
      (node (ref "U$1") (pin "12") (pinfunction "RCK_12") (pintype "bidirectional"))
      (node (ref "U$10") (pin "12") (pinfunction "RCK_12") (pintype "bidirectional"))
      (node (ref "U$11") (pin "12") (pinfunction "RCK_12") (pintype "bidirectional"))
      (node (ref "U$12") (pin "12") (pinfunction "RCK_12") (pintype "bidirectional"))
      (node (ref "U$13") (pin "12") (pinfunction "RCK_12") (pintype "bidirectional"))
      (node (ref "U$14") (pin "12") (pinfunction "RCK_12") (pintype "bidirectional"))
      (node (ref "U$15") (pin "12") (pinfunction "RCK_12") (pintype "bidirectional"))
      (node (ref "U$16") (pin "12") (pinfunction "RCK_12") (pintype "bidirectional"))
      (node (ref "U$17") (pin "12") (pinfunction "RCK_12") (pintype "bidirectional"))
      (node (ref "U$18") (pin "12") (pinfunction "RCK_12") (pintype "bidirectional"))
      (node (ref "U$19") (pin "12") (pinfunction "RCK_12") (pintype "bidirectional"))
      (node (ref "U$2") (pin "12") (pinfunction "RCK_12") (pintype "bidirectional"))
      (node (ref "U$20") (pin "12") (pinfunction "RCK_12") (pintype "bidirectional"))
      (node (ref "U$21") (pin "12") (pinfunction "RCK_12") (pintype "bidirectional"))
      (node (ref "U$22") (pin "12") (pinfunction "RCK_12") (pintype "bidirectional"))
      (node (ref "U$23") (pin "12") (pinfunction "RCK_12") (pintype "bidirectional"))
      (node (ref "U$3") (pin "12") (pinfunction "RCK_12") (pintype "bidirectional"))
      (node (ref "U$4") (pin "12") (pinfunction "RCK_12") (pintype "bidirectional"))
      (node (ref "U$5") (pin "12") (pinfunction "RCK_12") (pintype "bidirectional"))
      (node (ref "U$6") (pin "12") (pinfunction "RCK_12") (pintype "bidirectional"))
      (node (ref "U$7") (pin "12") (pinfunction "RCK_12") (pintype "bidirectional"))
      (node (ref "U$8") (pin "12") (pinfunction "RCK_12") (pintype "bidirectional"))
      (node (ref "U$9") (pin "12") (pinfunction "RCK_12") (pintype "bidirectional"))
    )
    (net (code "5") (name "N$16") (class "Default")
      (node (ref "U$1") (pin "11") (pinfunction "SCK_11") (pintype "bidirectional"))
      (node (ref "U$10") (pin "11") (pinfunction "SCK_11") (pintype "bidirectional"))
      (node (ref "U$11") (pin "11") (pinfunction "SCK_11") (pintype "bidirectional"))
      (node (ref "U$12") (pin "11") (pinfunction "SCK_11") (pintype "bidirectional"))
      (node (ref "U$13") (pin "11") (pinfunction "SCK_11") (pintype "bidirectional"))
      (node (ref "U$14") (pin "11") (pinfunction "SCK_11") (pintype "bidirectional"))
      (node (ref "U$15") (pin "11") (pinfunction "SCK_11") (pintype "bidirectional"))
      (node (ref "U$16") (pin "11") (pinfunction "SCK_11") (pintype "bidirectional"))
      (node (ref "U$17") (pin "11") (pinfunction "SCK_11") (pintype "bidirectional"))
      (node (ref "U$18") (pin "11") (pinfunction "SCK_11") (pintype "bidirectional"))
      (node (ref "U$19") (pin "11") (pinfunction "SCK_11") (pintype "bidirectional"))
      (node (ref "U$2") (pin "11") (pinfunction "SCK_11") (pintype "bidirectional"))
      (node (ref "U$20") (pin "11") (pinfunction "SCK_11") (pintype "bidirectional"))
      (node (ref "U$21") (pin "11") (pinfunction "SCK_11") (pintype "bidirectional"))
      (node (ref "U$22") (pin "11") (pinfunction "SCK_11") (pintype "bidirectional"))
      (node (ref "U$23") (pin "11") (pinfunction "SCK_11") (pintype "bidirectional"))
      (node (ref "U$3") (pin "11") (pinfunction "SCK_11") (pintype "bidirectional"))
      (node (ref "U$4") (pin "11") (pinfunction "SCK_11") (pintype "bidirectional"))
      (node (ref "U$5") (pin "11") (pinfunction "SCK_11") (pintype "bidirectional"))
      (node (ref "U$6") (pin "11") (pinfunction "SCK_11") (pintype "bidirectional"))
      (node (ref "U$7") (pin "11") (pinfunction "SCK_11") (pintype "bidirectional"))
      (node (ref "U$8") (pin "11") (pinfunction "SCK_11") (pintype "bidirectional"))
      (node (ref "U$9") (pin "11") (pinfunction "SCK_11") (pintype "bidirectional"))
    )
    (net (code "6") (name "N$17") (class "Default")
      (node (ref "U$1") (pin "10") (pinfunction "SCLR_10") (pintype "bidirectional"))
      (node (ref "U$10") (pin "10") (pinfunction "SCLR_10") (pintype "bidirectional"))
      (node (ref "U$11") (pin "10") (pinfunction "SCLR_10") (pintype "bidirectional"))
      (node (ref "U$12") (pin "10") (pinfunction "SCLR_10") (pintype "bidirectional"))
      (node (ref "U$13") (pin "10") (pinfunction "SCLR_10") (pintype "bidirectional"))
      (node (ref "U$14") (pin "10") (pinfunction "SCLR_10") (pintype "bidirectional"))
      (node (ref "U$15") (pin "10") (pinfunction "SCLR_10") (pintype "bidirectional"))
      (node (ref "U$16") (pin "10") (pinfunction "SCLR_10") (pintype "bidirectional"))
      (node (ref "U$17") (pin "10") (pinfunction "SCLR_10") (pintype "bidirectional"))
      (node (ref "U$18") (pin "10") (pinfunction "SCLR_10") (pintype "bidirectional"))
      (node (ref "U$19") (pin "10") (pinfunction "SCLR_10") (pintype "bidirectional"))
      (node (ref "U$2") (pin "10") (pinfunction "SCLR_10") (pintype "bidirectional"))
      (node (ref "U$20") (pin "10") (pinfunction "SCLR_10") (pintype "bidirectional"))
      (node (ref "U$21") (pin "10") (pinfunction "SCLR_10") (pintype "bidirectional"))
      (node (ref "U$22") (pin "10") (pinfunction "SCLR_10") (pintype "bidirectional"))
      (node (ref "U$23") (pin "10") (pinfunction "SCLR_10") (pintype "bidirectional"))
      (node (ref "U$3") (pin "10") (pinfunction "SCLR_10") (pintype "bidirectional"))
      (node (ref "U$4") (pin "10") (pinfunction "SCLR_10") (pintype "bidirectional"))
      (node (ref "U$5") (pin "10") (pinfunction "SCLR_10") (pintype "bidirectional"))
      (node (ref "U$6") (pin "10") (pinfunction "SCLR_10") (pintype "bidirectional"))
      (node (ref "U$7") (pin "10") (pinfunction "SCLR_10") (pintype "bidirectional"))
      (node (ref "U$8") (pin "10") (pinfunction "SCLR_10") (pintype "bidirectional"))
      (node (ref "U$9") (pin "10") (pinfunction "SCLR_10") (pintype "bidirectional"))
    )
    (net (code "7") (name "N$30") (class "Default")
      (node (ref "U$2") (pin "14") (pinfunction "SER_14") (pintype "bidirectional"))
    )
    (net (code "8") (name "N$31") (class "Default")
      (node (ref "U$3") (pin "14") (pinfunction "SER_14") (pintype "bidirectional"))
    )
    (net (code "9") (name "N$32") (class "Default")
      (node (ref "U$4") (pin "14") (pinfunction "SER_14") (pintype "bidirectional"))
    )
    (net (code "10") (name "N$33") (class "Default")
      (node (ref "U$5") (pin "14") (pinfunction "SER_14") (pintype "bidirectional"))
    )
    (net (code "11") (name "N$46") (class "Default")
      (node (ref "U$7") (pin "14") (pinfunction "SER_14") (pintype "bidirectional"))
    )
    (net (code "12") (name "N$47") (class "Default")
      (node (ref "U$8") (pin "14") (pinfunction "SER_14") (pintype "bidirectional"))
    )
    (net (code "13") (name "N$48") (class "Default")
      (node (ref "U$16") (pin "14") (pinfunction "SER_14") (pintype "bidirectional"))
    )
    (net (code "14") (name "N$49") (class "Default")
      (node (ref "U$15") (pin "14") (pinfunction "SER_14") (pintype "bidirectional"))
    )
    (net (code "15") (name "N$68") (class "Default")
      (node (ref "U$14") (pin "14") (pinfunction "SER_14") (pintype "bidirectional"))
    )
    (net (code "16") (name "N$75") (class "Default")
      (node (ref "U$13") (pin "14") (pinfunction "SER_14") (pintype "bidirectional"))
    )
    (net (code "17") (name "N$76") (class "Default")
      (node (ref "U$12") (pin "14") (pinfunction "SER_14") (pintype "bidirectional"))
    )
    (net (code "18") (name "N$77") (class "Default")
      (node (ref "U$11") (pin "14") (pinfunction "SER_14") (pintype "bidirectional"))
    )
    (net (code "19") (name "N$78") (class "Default")
      (node (ref "U$10") (pin "14") (pinfunction "SER_14") (pintype "bidirectional"))
    )
    (net (code "20") (name "N$121") (class "Default")
      (node (ref "U$9") (pin "14") (pinfunction "SER_14") (pintype "bidirectional"))
    )
    (net (code "21") (name "N$128") (class "Default")
      (node (ref "U$17") (pin "14") (pinfunction "SER_14") (pintype "bidirectional"))
    )
    (net (code "22") (name "N$129") (class "Default")
      (node (ref "U$18") (pin "14") (pinfunction "SER_14") (pintype "bidirectional"))
    )
    (net (code "23") (name "N$130") (class "Default")
      (node (ref "U$19") (pin "14") (pinfunction "SER_14") (pintype "bidirectional"))
    )
    (net (code "24") (name "N$131") (class "Default")
      (node (ref "U$20") (pin "14") (pinfunction "SER_14") (pintype "bidirectional"))
    )
    (net (code "25") (name "N$162") (class "Default")
      (node (ref "U$21") (pin "14") (pinfunction "SER_14") (pintype "bidirectional"))
    )
    (net (code "26") (name "N$163") (class "Default")
      (node (ref "U$22") (pin "14") (pinfunction "SER_14") (pintype "bidirectional"))
    )
    (net (code "27") (name "N$164") (class "Default")
      (node (ref "U$23") (pin "14") (pinfunction "SER_14") (pintype "bidirectional"))
    )
    (net (code "28") (name "N$165") (class "Default")
      (node (ref "U$6") (pin "14") (pinfunction "SER_14") (pintype "bidirectional"))
    )
    (net (code "29") (name "Net-(LED1-PadA)") (class "Default")
      (node (ref "LED1") (pin "A") (pinfunction "A_A") (pintype "passive"))
      (node (ref "R3") (pin "1") (pinfunction "1_1") (pintype "passive"))
    )
    (net (code "30") (name "Net-(LED2-PadA)") (class "Default")
      (node (ref "LED2") (pin "A") (pinfunction "A_A") (pintype "passive"))
      (node (ref "R4") (pin "1") (pinfunction "1_1") (pintype "passive"))
    )
    (net (code "31") (name "Net-(LED3-PadA)") (class "Default")
      (node (ref "LED3") (pin "A") (pinfunction "A_A") (pintype "passive"))
      (node (ref "R5") (pin "1") (pinfunction "1_1") (pintype "passive"))
    )
    (net (code "32") (name "Net-(LED4-PadA)") (class "Default")
      (node (ref "LED4") (pin "A") (pinfunction "A_A") (pintype "passive"))
      (node (ref "R6") (pin "1") (pinfunction "1_1") (pintype "passive"))
    )
    (net (code "33") (name "Net-(LED5-PadA)") (class "Default")
      (node (ref "LED5") (pin "A") (pinfunction "A_A") (pintype "passive"))
      (node (ref "R2") (pin "1") (pinfunction "1_1") (pintype "passive"))
    )
    (net (code "34") (name "Net-(LED6-PadA)") (class "Default")
      (node (ref "LED6") (pin "A") (pinfunction "A_A") (pintype "passive"))
      (node (ref "R1") (pin "1") (pinfunction "1_1") (pintype "passive"))
    )
    (net (code "35") (name "Net-(U$1-QA)") (class "Default")
      (node (ref "R1") (pin "2") (pinfunction "2_2") (pintype "passive"))
      (node (ref "U$1") (pin "15") (pinfunction "QA_15") (pintype "bidirectional"))
    )
    (net (code "36") (name "Net-(U$1-QB)") (class "Default")
      (node (ref "R2") (pin "2") (pinfunction "2_2") (pintype "passive"))
      (node (ref "U$1") (pin "1") (pinfunction "QB_1") (pintype "bidirectional"))
    )
    (net (code "37") (name "Net-(U$1-QC)") (class "Default")
      (node (ref "R3") (pin "2") (pinfunction "2_2") (pintype "passive"))
      (node (ref "U$1") (pin "2") (pinfunction "QC_2") (pintype "bidirectional"))
    )
    (net (code "38") (name "Net-(U$1-QD)") (class "Default")
      (node (ref "R4") (pin "2") (pinfunction "2_2") (pintype "passive"))
      (node (ref "U$1") (pin "3") (pinfunction "QD_3") (pintype "bidirectional"))
    )
    (net (code "39") (name "Net-(U$1-QE)") (class "Default")
      (node (ref "R5") (pin "2") (pinfunction "2_2") (pintype "passive"))
      (node (ref "U$1") (pin "4") (pinfunction "QE_4") (pintype "bidirectional"))
    )
    (net (code "40") (name "Net-(U$1-QF)") (class "Default")
      (node (ref "R6") (pin "2") (pinfunction "2_2") (pintype "passive"))
      (node (ref "U$1") (pin "5") (pinfunction "QF_5") (pintype "bidirectional"))
    )
    (net (code "41") (name "Net-(U$2-QA)") (class "Default")
      (node (ref "LED12") (pin "A") (pinfunction "A_A") (pintype "passive"))
      (node (ref "U$2") (pin "15") (pinfunction "QA_15") (pintype "bidirectional"))
    )
    (net (code "42") (name "Net-(U$2-QB)") (class "Default")
      (node (ref "LED11") (pin "A") (pinfunction "A_A") (pintype "passive"))
      (node (ref "U$2") (pin "1") (pinfunction "QB_1") (pintype "bidirectional"))
    )
    (net (code "43") (name "Net-(U$2-QC)") (class "Default")
      (node (ref "LED7") (pin "A") (pinfunction "A_A") (pintype "passive"))
      (node (ref "U$2") (pin "2") (pinfunction "QC_2") (pintype "bidirectional"))
    )
    (net (code "44") (name "Net-(U$2-QD)") (class "Default")
      (node (ref "LED8") (pin "A") (pinfunction "A_A") (pintype "passive"))
      (node (ref "U$2") (pin "3") (pinfunction "QD_3") (pintype "bidirectional"))
    )
    (net (code "45") (name "Net-(U$2-QE)") (class "Default")
      (node (ref "LED9") (pin "A") (pinfunction "A_A") (pintype "passive"))
      (node (ref "U$2") (pin "4") (pinfunction "QE_4") (pintype "bidirectional"))
    )
    (net (code "46") (name "Net-(U$2-QF)") (class "Default")
      (node (ref "LED10") (pin "A") (pinfunction "A_A") (pintype "passive"))
      (node (ref "U$2") (pin "5") (pinfunction "QF_5") (pintype "bidirectional"))
    )
    (net (code "47") (name "Net-(U$3-QA)") (class "Default")
      (node (ref "LED18") (pin "A") (pinfunction "A_A") (pintype "passive"))
      (node (ref "U$3") (pin "15") (pinfunction "QA_15") (pintype "bidirectional"))
    )
    (net (code "48") (name "Net-(U$3-QB)") (class "Default")
      (node (ref "LED17") (pin "A") (pinfunction "A_A") (pintype "passive"))
      (node (ref "U$3") (pin "1") (pinfunction "QB_1") (pintype "bidirectional"))
    )
    (net (code "49") (name "Net-(U$3-QC)") (class "Default")
      (node (ref "LED13") (pin "A") (pinfunction "A_A") (pintype "passive"))
      (node (ref "U$3") (pin "2") (pinfunction "QC_2") (pintype "bidirectional"))
    )
    (net (code "50") (name "Net-(U$3-QD)") (class "Default")
      (node (ref "LED14") (pin "A") (pinfunction "A_A") (pintype "passive"))
      (node (ref "U$3") (pin "3") (pinfunction "QD_3") (pintype "bidirectional"))
    )
    (net (code "51") (name "Net-(U$3-QE)") (class "Default")
      (node (ref "LED15") (pin "A") (pinfunction "A_A") (pintype "passive"))
      (node (ref "U$3") (pin "4") (pinfunction "QE_4") (pintype "bidirectional"))
    )
    (net (code "52") (name "Net-(U$3-QF)") (class "Default")
      (node (ref "LED16") (pin "A") (pinfunction "A_A") (pintype "passive"))
      (node (ref "U$3") (pin "5") (pinfunction "QF_5") (pintype "bidirectional"))
    )
    (net (code "53") (name "Net-(U$4-QA)") (class "Default")
      (node (ref "LED24") (pin "A") (pinfunction "A_A") (pintype "passive"))
      (node (ref "U$4") (pin "15") (pinfunction "QA_15") (pintype "bidirectional"))
    )
    (net (code "54") (name "Net-(U$4-QB)") (class "Default")
      (node (ref "LED23") (pin "A") (pinfunction "A_A") (pintype "passive"))
      (node (ref "U$4") (pin "1") (pinfunction "QB_1") (pintype "bidirectional"))
    )
    (net (code "55") (name "Net-(U$4-QC)") (class "Default")
      (node (ref "LED19") (pin "A") (pinfunction "A_A") (pintype "passive"))
      (node (ref "U$4") (pin "2") (pinfunction "QC_2") (pintype "bidirectional"))
    )
    (net (code "56") (name "Net-(U$4-QD)") (class "Default")
      (node (ref "LED20") (pin "A") (pinfunction "A_A") (pintype "passive"))
      (node (ref "U$4") (pin "3") (pinfunction "QD_3") (pintype "bidirectional"))
    )
    (net (code "57") (name "Net-(U$4-QE)") (class "Default")
      (node (ref "LED21") (pin "A") (pinfunction "A_A") (pintype "passive"))
      (node (ref "U$4") (pin "4") (pinfunction "QE_4") (pintype "bidirectional"))
    )
    (net (code "58") (name "Net-(U$4-QF)") (class "Default")
      (node (ref "LED22") (pin "A") (pinfunction "A_A") (pintype "passive"))
      (node (ref "U$4") (pin "5") (pinfunction "QF_5") (pintype "bidirectional"))
    )
    (net (code "59") (name "Net-(U$5-QA)") (class "Default")
      (node (ref "LED30") (pin "A") (pinfunction "A_A") (pintype "passive"))
      (node (ref "U$5") (pin "15") (pinfunction "QA_15") (pintype "bidirectional"))
    )
    (net (code "60") (name "Net-(U$5-QB)") (class "Default")
      (node (ref "LED29") (pin "A") (pinfunction "A_A") (pintype "passive"))
      (node (ref "U$5") (pin "1") (pinfunction "QB_1") (pintype "bidirectional"))
    )
    (net (code "61") (name "Net-(U$5-QC)") (class "Default")
      (node (ref "LED25") (pin "A") (pinfunction "A_A") (pintype "passive"))
      (node (ref "U$5") (pin "2") (pinfunction "QC_2") (pintype "bidirectional"))
    )
    (net (code "62") (name "Net-(U$5-QD)") (class "Default")
      (node (ref "LED26") (pin "A") (pinfunction "A_A") (pintype "passive"))
      (node (ref "U$5") (pin "3") (pinfunction "QD_3") (pintype "bidirectional"))
    )
    (net (code "63") (name "Net-(U$5-QE)") (class "Default")
      (node (ref "LED27") (pin "A") (pinfunction "A_A") (pintype "passive"))
      (node (ref "U$5") (pin "4") (pinfunction "QE_4") (pintype "bidirectional"))
    )
    (net (code "64") (name "Net-(U$5-QF)") (class "Default")
      (node (ref "LED28") (pin "A") (pinfunction "A_A") (pintype "passive"))
      (node (ref "U$5") (pin "5") (pinfunction "QF_5") (pintype "bidirectional"))
    )
    (net (code "65") (name "Net-(U$6-QA)") (class "Default")
      (node (ref "LED36") (pin "A") (pinfunction "A_A") (pintype "passive"))
      (node (ref "U$6") (pin "15") (pinfunction "QA_15") (pintype "bidirectional"))
    )
    (net (code "66") (name "Net-(U$6-QB)") (class "Default")
      (node (ref "LED35") (pin "A") (pinfunction "A_A") (pintype "passive"))
      (node (ref "U$6") (pin "1") (pinfunction "QB_1") (pintype "bidirectional"))
    )
    (net (code "67") (name "Net-(U$6-QC)") (class "Default")
      (node (ref "LED31") (pin "A") (pinfunction "A_A") (pintype "passive"))
      (node (ref "U$6") (pin "2") (pinfunction "QC_2") (pintype "bidirectional"))
    )
    (net (code "68") (name "Net-(U$6-QD)") (class "Default")
      (node (ref "LED32") (pin "A") (pinfunction "A_A") (pintype "passive"))
      (node (ref "U$6") (pin "3") (pinfunction "QD_3") (pintype "bidirectional"))
    )
    (net (code "69") (name "Net-(U$6-QE)") (class "Default")
      (node (ref "LED33") (pin "A") (pinfunction "A_A") (pintype "passive"))
      (node (ref "U$6") (pin "4") (pinfunction "QE_4") (pintype "bidirectional"))
    )
    (net (code "70") (name "Net-(U$6-QF)") (class "Default")
      (node (ref "LED34") (pin "A") (pinfunction "A_A") (pintype "passive"))
      (node (ref "U$6") (pin "5") (pinfunction "QF_5") (pintype "bidirectional"))
    )
    (net (code "71") (name "Net-(U$7-QA)") (class "Default")
      (node (ref "LED42") (pin "A") (pinfunction "A_A") (pintype "passive"))
      (node (ref "U$7") (pin "15") (pinfunction "QA_15") (pintype "bidirectional"))
    )
    (net (code "72") (name "Net-(U$7-QB)") (class "Default")
      (node (ref "LED41") (pin "A") (pinfunction "A_A") (pintype "passive"))
      (node (ref "U$7") (pin "1") (pinfunction "QB_1") (pintype "bidirectional"))
    )
    (net (code "73") (name "Net-(U$7-QC)") (class "Default")
      (node (ref "LED37") (pin "A") (pinfunction "A_A") (pintype "passive"))
      (node (ref "U$7") (pin "2") (pinfunction "QC_2") (pintype "bidirectional"))
    )
    (net (code "74") (name "Net-(U$7-QD)") (class "Default")
      (node (ref "LED38") (pin "A") (pinfunction "A_A") (pintype "passive"))
      (node (ref "U$7") (pin "3") (pinfunction "QD_3") (pintype "bidirectional"))
    )
    (net (code "75") (name "Net-(U$7-QE)") (class "Default")
      (node (ref "LED39") (pin "A") (pinfunction "A_A") (pintype "passive"))
      (node (ref "U$7") (pin "4") (pinfunction "QE_4") (pintype "bidirectional"))
    )
    (net (code "76") (name "Net-(U$7-QF)") (class "Default")
      (node (ref "LED40") (pin "A") (pinfunction "A_A") (pintype "passive"))
      (node (ref "U$7") (pin "5") (pinfunction "QF_5") (pintype "bidirectional"))
    )
    (net (code "77") (name "Net-(U$8-QA)") (class "Default")
      (node (ref "LED48") (pin "A") (pinfunction "A_A") (pintype "passive"))
      (node (ref "U$8") (pin "15") (pinfunction "QA_15") (pintype "bidirectional"))
    )
    (net (code "78") (name "Net-(U$8-QB)") (class "Default")
      (node (ref "LED47") (pin "A") (pinfunction "A_A") (pintype "passive"))
      (node (ref "U$8") (pin "1") (pinfunction "QB_1") (pintype "bidirectional"))
    )
    (net (code "79") (name "Net-(U$8-QC)") (class "Default")
      (node (ref "LED43") (pin "A") (pinfunction "A_A") (pintype "passive"))
      (node (ref "U$8") (pin "2") (pinfunction "QC_2") (pintype "bidirectional"))
    )
    (net (code "80") (name "Net-(U$8-QD)") (class "Default")
      (node (ref "LED44") (pin "A") (pinfunction "A_A") (pintype "passive"))
      (node (ref "U$8") (pin "3") (pinfunction "QD_3") (pintype "bidirectional"))
    )
    (net (code "81") (name "Net-(U$8-QE)") (class "Default")
      (node (ref "LED45") (pin "A") (pinfunction "A_A") (pintype "passive"))
      (node (ref "U$8") (pin "4") (pinfunction "QE_4") (pintype "bidirectional"))
    )
    (net (code "82") (name "Net-(U$8-QF)") (class "Default")
      (node (ref "LED46") (pin "A") (pinfunction "A_A") (pintype "passive"))
      (node (ref "U$8") (pin "5") (pinfunction "QF_5") (pintype "bidirectional"))
    )
    (net (code "83") (name "Net-(U$9-QA)") (class "Default")
      (node (ref "LED54") (pin "A") (pinfunction "A_A") (pintype "passive"))
      (node (ref "U$9") (pin "15") (pinfunction "QA_15") (pintype "bidirectional"))
    )
    (net (code "84") (name "Net-(U$9-QB)") (class "Default")
      (node (ref "LED53") (pin "A") (pinfunction "A_A") (pintype "passive"))
      (node (ref "U$9") (pin "1") (pinfunction "QB_1") (pintype "bidirectional"))
    )
    (net (code "85") (name "Net-(U$9-QC)") (class "Default")
      (node (ref "LED49") (pin "A") (pinfunction "A_A") (pintype "passive"))
      (node (ref "U$9") (pin "2") (pinfunction "QC_2") (pintype "bidirectional"))
    )
    (net (code "86") (name "Net-(U$9-QD)") (class "Default")
      (node (ref "LED50") (pin "A") (pinfunction "A_A") (pintype "passive"))
      (node (ref "U$9") (pin "3") (pinfunction "QD_3") (pintype "bidirectional"))
    )
    (net (code "87") (name "Net-(U$9-QE)") (class "Default")
      (node (ref "LED51") (pin "A") (pinfunction "A_A") (pintype "passive"))
      (node (ref "U$9") (pin "4") (pinfunction "QE_4") (pintype "bidirectional"))
    )
    (net (code "88") (name "Net-(U$9-QF)") (class "Default")
      (node (ref "LED52") (pin "A") (pinfunction "A_A") (pintype "passive"))
      (node (ref "U$9") (pin "5") (pinfunction "QF_5") (pintype "bidirectional"))
    )
    (net (code "89") (name "Net-(U$10-QA)") (class "Default")
      (node (ref "LED60") (pin "A") (pinfunction "A_A") (pintype "passive"))
      (node (ref "U$10") (pin "15") (pinfunction "QA_15") (pintype "bidirectional"))
    )
    (net (code "90") (name "Net-(U$10-QB)") (class "Default")
      (node (ref "LED59") (pin "A") (pinfunction "A_A") (pintype "passive"))
      (node (ref "U$10") (pin "1") (pinfunction "QB_1") (pintype "bidirectional"))
    )
    (net (code "91") (name "Net-(U$10-QC)") (class "Default")
      (node (ref "LED55") (pin "A") (pinfunction "A_A") (pintype "passive"))
      (node (ref "U$10") (pin "2") (pinfunction "QC_2") (pintype "bidirectional"))
    )
    (net (code "92") (name "Net-(U$10-QD)") (class "Default")
      (node (ref "LED56") (pin "A") (pinfunction "A_A") (pintype "passive"))
      (node (ref "U$10") (pin "3") (pinfunction "QD_3") (pintype "bidirectional"))
    )
    (net (code "93") (name "Net-(U$10-QE)") (class "Default")
      (node (ref "LED57") (pin "A") (pinfunction "A_A") (pintype "passive"))
      (node (ref "U$10") (pin "4") (pinfunction "QE_4") (pintype "bidirectional"))
    )
    (net (code "94") (name "Net-(U$10-QF)") (class "Default")
      (node (ref "LED58") (pin "A") (pinfunction "A_A") (pintype "passive"))
      (node (ref "U$10") (pin "5") (pinfunction "QF_5") (pintype "bidirectional"))
    )
    (net (code "95") (name "Net-(U$11-QA)") (class "Default")
      (node (ref "LED66") (pin "A") (pinfunction "A_A") (pintype "passive"))
      (node (ref "U$11") (pin "15") (pinfunction "QA_15") (pintype "bidirectional"))
    )
    (net (code "96") (name "Net-(U$11-QB)") (class "Default")
      (node (ref "LED65") (pin "A") (pinfunction "A_A") (pintype "passive"))
      (node (ref "U$11") (pin "1") (pinfunction "QB_1") (pintype "bidirectional"))
    )
    (net (code "97") (name "Net-(U$11-QC)") (class "Default")
      (node (ref "LED61") (pin "A") (pinfunction "A_A") (pintype "passive"))
      (node (ref "U$11") (pin "2") (pinfunction "QC_2") (pintype "bidirectional"))
    )
    (net (code "98") (name "Net-(U$11-QD)") (class "Default")
      (node (ref "LED62") (pin "A") (pinfunction "A_A") (pintype "passive"))
      (node (ref "U$11") (pin "3") (pinfunction "QD_3") (pintype "bidirectional"))
    )
    (net (code "99") (name "Net-(U$11-QE)") (class "Default")
      (node (ref "LED63") (pin "A") (pinfunction "A_A") (pintype "passive"))
      (node (ref "U$11") (pin "4") (pinfunction "QE_4") (pintype "bidirectional"))
    )
    (net (code "100") (name "Net-(U$11-QF)") (class "Default")
      (node (ref "LED64") (pin "A") (pinfunction "A_A") (pintype "passive"))
      (node (ref "U$11") (pin "5") (pinfunction "QF_5") (pintype "bidirectional"))
    )
    (net (code "101") (name "Net-(U$12-QA)") (class "Default")
      (node (ref "LED72") (pin "A") (pinfunction "A_A") (pintype "passive"))
      (node (ref "U$12") (pin "15") (pinfunction "QA_15") (pintype "bidirectional"))
    )
    (net (code "102") (name "Net-(U$12-QB)") (class "Default")
      (node (ref "LED71") (pin "A") (pinfunction "A_A") (pintype "passive"))
      (node (ref "U$12") (pin "1") (pinfunction "QB_1") (pintype "bidirectional"))
    )
    (net (code "103") (name "Net-(U$12-QC)") (class "Default")
      (node (ref "LED67") (pin "A") (pinfunction "A_A") (pintype "passive"))
      (node (ref "U$12") (pin "2") (pinfunction "QC_2") (pintype "bidirectional"))
    )
    (net (code "104") (name "Net-(U$12-QD)") (class "Default")
      (node (ref "LED68") (pin "A") (pinfunction "A_A") (pintype "passive"))
      (node (ref "U$12") (pin "3") (pinfunction "QD_3") (pintype "bidirectional"))
    )
    (net (code "105") (name "Net-(U$12-QE)") (class "Default")
      (node (ref "LED69") (pin "A") (pinfunction "A_A") (pintype "passive"))
      (node (ref "U$12") (pin "4") (pinfunction "QE_4") (pintype "bidirectional"))
    )
    (net (code "106") (name "Net-(U$12-QF)") (class "Default")
      (node (ref "LED70") (pin "A") (pinfunction "A_A") (pintype "passive"))
      (node (ref "U$12") (pin "5") (pinfunction "QF_5") (pintype "bidirectional"))
    )
    (net (code "107") (name "Net-(U$13-QA)") (class "Default")
      (node (ref "LED78") (pin "A") (pinfunction "A_A") (pintype "passive"))
      (node (ref "U$13") (pin "15") (pinfunction "QA_15") (pintype "bidirectional"))
    )
    (net (code "108") (name "Net-(U$13-QB)") (class "Default")
      (node (ref "LED77") (pin "A") (pinfunction "A_A") (pintype "passive"))
      (node (ref "U$13") (pin "1") (pinfunction "QB_1") (pintype "bidirectional"))
    )
    (net (code "109") (name "Net-(U$13-QC)") (class "Default")
      (node (ref "LED73") (pin "A") (pinfunction "A_A") (pintype "passive"))
      (node (ref "U$13") (pin "2") (pinfunction "QC_2") (pintype "bidirectional"))
    )
    (net (code "110") (name "Net-(U$13-QD)") (class "Default")
      (node (ref "LED74") (pin "A") (pinfunction "A_A") (pintype "passive"))
      (node (ref "U$13") (pin "3") (pinfunction "QD_3") (pintype "bidirectional"))
    )
    (net (code "111") (name "Net-(U$13-QE)") (class "Default")
      (node (ref "LED75") (pin "A") (pinfunction "A_A") (pintype "passive"))
      (node (ref "U$13") (pin "4") (pinfunction "QE_4") (pintype "bidirectional"))
    )
    (net (code "112") (name "Net-(U$13-QF)") (class "Default")
      (node (ref "LED76") (pin "A") (pinfunction "A_A") (pintype "passive"))
      (node (ref "U$13") (pin "5") (pinfunction "QF_5") (pintype "bidirectional"))
    )
    (net (code "113") (name "Net-(U$14-QA)") (class "Default")
      (node (ref "LED84") (pin "A") (pinfunction "A_A") (pintype "passive"))
      (node (ref "U$14") (pin "15") (pinfunction "QA_15") (pintype "bidirectional"))
    )
    (net (code "114") (name "Net-(U$14-QB)") (class "Default")
      (node (ref "LED83") (pin "A") (pinfunction "A_A") (pintype "passive"))
      (node (ref "U$14") (pin "1") (pinfunction "QB_1") (pintype "bidirectional"))
    )
    (net (code "115") (name "Net-(U$14-QC)") (class "Default")
      (node (ref "LED79") (pin "A") (pinfunction "A_A") (pintype "passive"))
      (node (ref "U$14") (pin "2") (pinfunction "QC_2") (pintype "bidirectional"))
    )
    (net (code "116") (name "Net-(U$14-QD)") (class "Default")
      (node (ref "LED80") (pin "A") (pinfunction "A_A") (pintype "passive"))
      (node (ref "U$14") (pin "3") (pinfunction "QD_3") (pintype "bidirectional"))
    )
    (net (code "117") (name "Net-(U$14-QE)") (class "Default")
      (node (ref "LED81") (pin "A") (pinfunction "A_A") (pintype "passive"))
      (node (ref "U$14") (pin "4") (pinfunction "QE_4") (pintype "bidirectional"))
    )
    (net (code "118") (name "Net-(U$14-QF)") (class "Default")
      (node (ref "LED82") (pin "A") (pinfunction "A_A") (pintype "passive"))
      (node (ref "U$14") (pin "5") (pinfunction "QF_5") (pintype "bidirectional"))
    )
    (net (code "119") (name "Net-(U$15-QA)") (class "Default")
      (node (ref "LED90") (pin "A") (pinfunction "A_A") (pintype "passive"))
      (node (ref "U$15") (pin "15") (pinfunction "QA_15") (pintype "bidirectional"))
    )
    (net (code "120") (name "Net-(U$15-QB)") (class "Default")
      (node (ref "LED89") (pin "A") (pinfunction "A_A") (pintype "passive"))
      (node (ref "U$15") (pin "1") (pinfunction "QB_1") (pintype "bidirectional"))
    )
    (net (code "121") (name "Net-(U$15-QC)") (class "Default")
      (node (ref "LED85") (pin "A") (pinfunction "A_A") (pintype "passive"))
      (node (ref "U$15") (pin "2") (pinfunction "QC_2") (pintype "bidirectional"))
    )
    (net (code "122") (name "Net-(U$15-QD)") (class "Default")
      (node (ref "LED86") (pin "A") (pinfunction "A_A") (pintype "passive"))
      (node (ref "U$15") (pin "3") (pinfunction "QD_3") (pintype "bidirectional"))
    )
    (net (code "123") (name "Net-(U$15-QE)") (class "Default")
      (node (ref "LED87") (pin "A") (pinfunction "A_A") (pintype "passive"))
      (node (ref "U$15") (pin "4") (pinfunction "QE_4") (pintype "bidirectional"))
    )
    (net (code "124") (name "Net-(U$15-QF)") (class "Default")
      (node (ref "LED88") (pin "A") (pinfunction "A_A") (pintype "passive"))
      (node (ref "U$15") (pin "5") (pinfunction "QF_5") (pintype "bidirectional"))
    )
    (net (code "125") (name "Net-(U$16-QA)") (class "Default")
      (node (ref "LED96") (pin "A") (pinfunction "A_A") (pintype "passive"))
      (node (ref "U$16") (pin "15") (pinfunction "QA_15") (pintype "bidirectional"))
    )
    (net (code "126") (name "Net-(U$16-QB)") (class "Default")
      (node (ref "LED95") (pin "A") (pinfunction "A_A") (pintype "passive"))
      (node (ref "U$16") (pin "1") (pinfunction "QB_1") (pintype "bidirectional"))
    )
    (net (code "127") (name "Net-(U$16-QC)") (class "Default")
      (node (ref "LED91") (pin "A") (pinfunction "A_A") (pintype "passive"))
      (node (ref "U$16") (pin "2") (pinfunction "QC_2") (pintype "bidirectional"))
    )
    (net (code "128") (name "Net-(U$16-QD)") (class "Default")
      (node (ref "LED92") (pin "A") (pinfunction "A_A") (pintype "passive"))
      (node (ref "U$16") (pin "3") (pinfunction "QD_3") (pintype "bidirectional"))
    )
    (net (code "129") (name "Net-(U$16-QE)") (class "Default")
      (node (ref "LED93") (pin "A") (pinfunction "A_A") (pintype "passive"))
      (node (ref "U$16") (pin "4") (pinfunction "QE_4") (pintype "bidirectional"))
    )
    (net (code "130") (name "Net-(U$16-QF)") (class "Default")
      (node (ref "LED94") (pin "A") (pinfunction "A_A") (pintype "passive"))
      (node (ref "U$16") (pin "5") (pinfunction "QF_5") (pintype "bidirectional"))
    )
    (net (code "131") (name "Net-(U$17-QA)") (class "Default")
      (node (ref "LED102") (pin "A") (pinfunction "A_A") (pintype "passive"))
      (node (ref "U$17") (pin "15") (pinfunction "QA_15") (pintype "bidirectional"))
    )
    (net (code "132") (name "Net-(U$17-QB)") (class "Default")
      (node (ref "LED101") (pin "A") (pinfunction "A_A") (pintype "passive"))
      (node (ref "U$17") (pin "1") (pinfunction "QB_1") (pintype "bidirectional"))
    )
    (net (code "133") (name "Net-(U$17-QC)") (class "Default")
      (node (ref "LED97") (pin "A") (pinfunction "A_A") (pintype "passive"))
      (node (ref "U$17") (pin "2") (pinfunction "QC_2") (pintype "bidirectional"))
    )
    (net (code "134") (name "Net-(U$17-QD)") (class "Default")
      (node (ref "LED98") (pin "A") (pinfunction "A_A") (pintype "passive"))
      (node (ref "U$17") (pin "3") (pinfunction "QD_3") (pintype "bidirectional"))
    )
    (net (code "135") (name "Net-(U$17-QE)") (class "Default")
      (node (ref "LED99") (pin "A") (pinfunction "A_A") (pintype "passive"))
      (node (ref "U$17") (pin "4") (pinfunction "QE_4") (pintype "bidirectional"))
    )
    (net (code "136") (name "Net-(U$17-QF)") (class "Default")
      (node (ref "LED100") (pin "A") (pinfunction "A_A") (pintype "passive"))
      (node (ref "U$17") (pin "5") (pinfunction "QF_5") (pintype "bidirectional"))
    )
    (net (code "137") (name "Net-(U$18-QA)") (class "Default")
      (node (ref "LED108") (pin "A") (pinfunction "A_A") (pintype "passive"))
      (node (ref "U$18") (pin "15") (pinfunction "QA_15") (pintype "bidirectional"))
    )
    (net (code "138") (name "Net-(U$18-QB)") (class "Default")
      (node (ref "LED107") (pin "A") (pinfunction "A_A") (pintype "passive"))
      (node (ref "U$18") (pin "1") (pinfunction "QB_1") (pintype "bidirectional"))
    )
    (net (code "139") (name "Net-(U$18-QC)") (class "Default")
      (node (ref "LED103") (pin "A") (pinfunction "A_A") (pintype "passive"))
      (node (ref "U$18") (pin "2") (pinfunction "QC_2") (pintype "bidirectional"))
    )
    (net (code "140") (name "Net-(U$18-QD)") (class "Default")
      (node (ref "LED104") (pin "A") (pinfunction "A_A") (pintype "passive"))
      (node (ref "U$18") (pin "3") (pinfunction "QD_3") (pintype "bidirectional"))
    )
    (net (code "141") (name "Net-(U$18-QE)") (class "Default")
      (node (ref "LED105") (pin "A") (pinfunction "A_A") (pintype "passive"))
      (node (ref "U$18") (pin "4") (pinfunction "QE_4") (pintype "bidirectional"))
    )
    (net (code "142") (name "Net-(U$18-QF)") (class "Default")
      (node (ref "LED106") (pin "A") (pinfunction "A_A") (pintype "passive"))
      (node (ref "U$18") (pin "5") (pinfunction "QF_5") (pintype "bidirectional"))
    )
    (net (code "143") (name "Net-(U$19-QA)") (class "Default")
      (node (ref "LED114") (pin "A") (pinfunction "A_A") (pintype "passive"))
      (node (ref "U$19") (pin "15") (pinfunction "QA_15") (pintype "bidirectional"))
    )
    (net (code "144") (name "Net-(U$19-QB)") (class "Default")
      (node (ref "LED113") (pin "A") (pinfunction "A_A") (pintype "passive"))
      (node (ref "U$19") (pin "1") (pinfunction "QB_1") (pintype "bidirectional"))
    )
    (net (code "145") (name "Net-(U$19-QC)") (class "Default")
      (node (ref "LED109") (pin "A") (pinfunction "A_A") (pintype "passive"))
      (node (ref "U$19") (pin "2") (pinfunction "QC_2") (pintype "bidirectional"))
    )
    (net (code "146") (name "Net-(U$19-QD)") (class "Default")
      (node (ref "LED110") (pin "A") (pinfunction "A_A") (pintype "passive"))
      (node (ref "U$19") (pin "3") (pinfunction "QD_3") (pintype "bidirectional"))
    )
    (net (code "147") (name "Net-(U$19-QE)") (class "Default")
      (node (ref "LED111") (pin "A") (pinfunction "A_A") (pintype "passive"))
      (node (ref "U$19") (pin "4") (pinfunction "QE_4") (pintype "bidirectional"))
    )
    (net (code "148") (name "Net-(U$19-QF)") (class "Default")
      (node (ref "LED112") (pin "A") (pinfunction "A_A") (pintype "passive"))
      (node (ref "U$19") (pin "5") (pinfunction "QF_5") (pintype "bidirectional"))
    )
    (net (code "149") (name "Net-(U$20-QA)") (class "Default")
      (node (ref "LED120") (pin "A") (pinfunction "A_A") (pintype "passive"))
      (node (ref "U$20") (pin "15") (pinfunction "QA_15") (pintype "bidirectional"))
    )
    (net (code "150") (name "Net-(U$20-QB)") (class "Default")
      (node (ref "LED119") (pin "A") (pinfunction "A_A") (pintype "passive"))
      (node (ref "U$20") (pin "1") (pinfunction "QB_1") (pintype "bidirectional"))
    )
    (net (code "151") (name "Net-(U$20-QC)") (class "Default")
      (node (ref "LED115") (pin "A") (pinfunction "A_A") (pintype "passive"))
      (node (ref "U$20") (pin "2") (pinfunction "QC_2") (pintype "bidirectional"))
    )
    (net (code "152") (name "Net-(U$20-QD)") (class "Default")
      (node (ref "LED116") (pin "A") (pinfunction "A_A") (pintype "passive"))
      (node (ref "U$20") (pin "3") (pinfunction "QD_3") (pintype "bidirectional"))
    )
    (net (code "153") (name "Net-(U$20-QE)") (class "Default")
      (node (ref "LED117") (pin "A") (pinfunction "A_A") (pintype "passive"))
      (node (ref "U$20") (pin "4") (pinfunction "QE_4") (pintype "bidirectional"))
    )
    (net (code "154") (name "Net-(U$20-QF)") (class "Default")
      (node (ref "LED118") (pin "A") (pinfunction "A_A") (pintype "passive"))
      (node (ref "U$20") (pin "5") (pinfunction "QF_5") (pintype "bidirectional"))
    )
    (net (code "155") (name "Net-(U$21-QA)") (class "Default")
      (node (ref "LED126") (pin "A") (pinfunction "A_A") (pintype "passive"))
      (node (ref "U$21") (pin "15") (pinfunction "QA_15") (pintype "bidirectional"))
    )
    (net (code "156") (name "Net-(U$21-QB)") (class "Default")
      (node (ref "LED125") (pin "A") (pinfunction "A_A") (pintype "passive"))
      (node (ref "U$21") (pin "1") (pinfunction "QB_1") (pintype "bidirectional"))
    )
    (net (code "157") (name "Net-(U$21-QC)") (class "Default")
      (node (ref "LED121") (pin "A") (pinfunction "A_A") (pintype "passive"))
      (node (ref "U$21") (pin "2") (pinfunction "QC_2") (pintype "bidirectional"))
    )
    (net (code "158") (name "Net-(U$21-QD)") (class "Default")
      (node (ref "LED122") (pin "A") (pinfunction "A_A") (pintype "passive"))
      (node (ref "U$21") (pin "3") (pinfunction "QD_3") (pintype "bidirectional"))
    )
    (net (code "159") (name "Net-(U$21-QE)") (class "Default")
      (node (ref "LED123") (pin "A") (pinfunction "A_A") (pintype "passive"))
      (node (ref "U$21") (pin "4") (pinfunction "QE_4") (pintype "bidirectional"))
    )
    (net (code "160") (name "Net-(U$21-QF)") (class "Default")
      (node (ref "LED124") (pin "A") (pinfunction "A_A") (pintype "passive"))
      (node (ref "U$21") (pin "5") (pinfunction "QF_5") (pintype "bidirectional"))
    )
    (net (code "161") (name "Net-(U$22-QA)") (class "Default")
      (node (ref "LED132") (pin "A") (pinfunction "A_A") (pintype "passive"))
      (node (ref "U$22") (pin "15") (pinfunction "QA_15") (pintype "bidirectional"))
    )
    (net (code "162") (name "Net-(U$22-QB)") (class "Default")
      (node (ref "LED131") (pin "A") (pinfunction "A_A") (pintype "passive"))
      (node (ref "U$22") (pin "1") (pinfunction "QB_1") (pintype "bidirectional"))
    )
    (net (code "163") (name "Net-(U$22-QC)") (class "Default")
      (node (ref "LED127") (pin "A") (pinfunction "A_A") (pintype "passive"))
      (node (ref "U$22") (pin "2") (pinfunction "QC_2") (pintype "bidirectional"))
    )
    (net (code "164") (name "Net-(U$22-QD)") (class "Default")
      (node (ref "LED128") (pin "A") (pinfunction "A_A") (pintype "passive"))
      (node (ref "U$22") (pin "3") (pinfunction "QD_3") (pintype "bidirectional"))
    )
    (net (code "165") (name "Net-(U$22-QE)") (class "Default")
      (node (ref "LED129") (pin "A") (pinfunction "A_A") (pintype "passive"))
      (node (ref "U$22") (pin "4") (pinfunction "QE_4") (pintype "bidirectional"))
    )
    (net (code "166") (name "Net-(U$22-QF)") (class "Default")
      (node (ref "LED130") (pin "A") (pinfunction "A_A") (pintype "passive"))
      (node (ref "U$22") (pin "5") (pinfunction "QF_5") (pintype "bidirectional"))
    )
    (net (code "167") (name "Net-(U$23-QA)") (class "Default")
      (node (ref "LED138") (pin "A") (pinfunction "A_A") (pintype "passive"))
      (node (ref "U$23") (pin "15") (pinfunction "QA_15") (pintype "bidirectional"))
    )
    (net (code "168") (name "Net-(U$23-QB)") (class "Default")
      (node (ref "LED137") (pin "A") (pinfunction "A_A") (pintype "passive"))
      (node (ref "U$23") (pin "1") (pinfunction "QB_1") (pintype "bidirectional"))
    )
    (net (code "169") (name "Net-(U$23-QC)") (class "Default")
      (node (ref "LED133") (pin "A") (pinfunction "A_A") (pintype "passive"))
      (node (ref "U$23") (pin "2") (pinfunction "QC_2") (pintype "bidirectional"))
    )
    (net (code "170") (name "Net-(U$23-QD)") (class "Default")
      (node (ref "LED134") (pin "A") (pinfunction "A_A") (pintype "passive"))
      (node (ref "U$23") (pin "3") (pinfunction "QD_3") (pintype "bidirectional"))
    )
    (net (code "171") (name "Net-(U$23-QE)") (class "Default")
      (node (ref "LED135") (pin "A") (pinfunction "A_A") (pintype "passive"))
      (node (ref "U$23") (pin "4") (pinfunction "QE_4") (pintype "bidirectional"))
    )
    (net (code "172") (name "Net-(U$23-QF)") (class "Default")
      (node (ref "LED136") (pin "A") (pinfunction "A_A") (pintype "passive"))
      (node (ref "U$23") (pin "5") (pinfunction "QF_5") (pintype "bidirectional"))
    )
    (net (code "173") (name "VCC") (class "Default")
      (node (ref "U$1") (pin "16") (pinfunction "VCC_16") (pintype "bidirectional"))
      (node (ref "U$10") (pin "16") (pinfunction "VCC_16") (pintype "bidirectional"))
      (node (ref "U$11") (pin "16") (pinfunction "VCC_16") (pintype "bidirectional"))
      (node (ref "U$12") (pin "16") (pinfunction "VCC_16") (pintype "bidirectional"))
      (node (ref "U$13") (pin "16") (pinfunction "VCC_16") (pintype "bidirectional"))
      (node (ref "U$14") (pin "16") (pinfunction "VCC_16") (pintype "bidirectional"))
      (node (ref "U$15") (pin "16") (pinfunction "VCC_16") (pintype "bidirectional"))
      (node (ref "U$16") (pin "16") (pinfunction "VCC_16") (pintype "bidirectional"))
      (node (ref "U$17") (pin "16") (pinfunction "VCC_16") (pintype "bidirectional"))
      (node (ref "U$18") (pin "16") (pinfunction "VCC_16") (pintype "bidirectional"))
      (node (ref "U$19") (pin "16") (pinfunction "VCC_16") (pintype "bidirectional"))
      (node (ref "U$2") (pin "16") (pinfunction "VCC_16") (pintype "bidirectional"))
      (node (ref "U$20") (pin "16") (pinfunction "VCC_16") (pintype "bidirectional"))
      (node (ref "U$21") (pin "16") (pinfunction "VCC_16") (pintype "bidirectional"))
      (node (ref "U$22") (pin "16") (pinfunction "VCC_16") (pintype "bidirectional"))
      (node (ref "U$23") (pin "16") (pinfunction "VCC_16") (pintype "bidirectional"))
      (node (ref "U$3") (pin "16") (pinfunction "VCC_16") (pintype "bidirectional"))
      (node (ref "U$4") (pin "16") (pinfunction "VCC_16") (pintype "bidirectional"))
      (node (ref "U$5") (pin "16") (pinfunction "VCC_16") (pintype "bidirectional"))
      (node (ref "U$6") (pin "16") (pinfunction "VCC_16") (pintype "bidirectional"))
      (node (ref "U$7") (pin "16") (pinfunction "VCC_16") (pintype "bidirectional"))
      (node (ref "U$8") (pin "16") (pinfunction "VCC_16") (pintype "bidirectional"))
      (node (ref "U$9") (pin "16") (pinfunction "VCC_16") (pintype "bidirectional"))
    )
    (net (code "174") (name "unconnected-(LED7-PadC)") (class "Default")
      (node (ref "LED7") (pin "C") (pinfunction "C_C") (pintype "passive"))
    )
    (net (code "175") (name "unconnected-(LED8-PadC)") (class "Default")
      (node (ref "LED8") (pin "C") (pinfunction "C_C") (pintype "passive"))
    )
    (net (code "176") (name "unconnected-(LED9-PadC)") (class "Default")
      (node (ref "LED9") (pin "C") (pinfunction "C_C") (pintype "passive"))
    )
    (net (code "177") (name "unconnected-(LED10-PadC)") (class "Default")
      (node (ref "LED10") (pin "C") (pinfunction "C_C") (pintype "passive"))
    )
    (net (code "178") (name "unconnected-(LED11-PadC)") (class "Default")
      (node (ref "LED11") (pin "C") (pinfunction "C_C") (pintype "passive"))
    )
    (net (code "179") (name "unconnected-(LED12-PadC)") (class "Default")
      (node (ref "LED12") (pin "C") (pinfunction "C_C") (pintype "passive"))
    )
    (net (code "180") (name "unconnected-(LED13-PadC)") (class "Default")
      (node (ref "LED13") (pin "C") (pinfunction "C_C") (pintype "passive"))
    )
    (net (code "181") (name "unconnected-(LED14-PadC)") (class "Default")
      (node (ref "LED14") (pin "C") (pinfunction "C_C") (pintype "passive"))
    )
    (net (code "182") (name "unconnected-(LED15-PadC)") (class "Default")
      (node (ref "LED15") (pin "C") (pinfunction "C_C") (pintype "passive"))
    )
    (net (code "183") (name "unconnected-(LED16-PadC)") (class "Default")
      (node (ref "LED16") (pin "C") (pinfunction "C_C") (pintype "passive"))
    )
    (net (code "184") (name "unconnected-(LED17-PadC)") (class "Default")
      (node (ref "LED17") (pin "C") (pinfunction "C_C") (pintype "passive"))
    )
    (net (code "185") (name "unconnected-(LED18-PadC)") (class "Default")
      (node (ref "LED18") (pin "C") (pinfunction "C_C") (pintype "passive"))
    )
    (net (code "186") (name "unconnected-(LED19-PadC)") (class "Default")
      (node (ref "LED19") (pin "C") (pinfunction "C_C") (pintype "passive"))
    )
    (net (code "187") (name "unconnected-(LED20-PadC)") (class "Default")
      (node (ref "LED20") (pin "C") (pinfunction "C_C") (pintype "passive"))
    )
    (net (code "188") (name "unconnected-(LED21-PadC)") (class "Default")
      (node (ref "LED21") (pin "C") (pinfunction "C_C") (pintype "passive"))
    )
    (net (code "189") (name "unconnected-(LED22-PadC)") (class "Default")
      (node (ref "LED22") (pin "C") (pinfunction "C_C") (pintype "passive"))
    )
    (net (code "190") (name "unconnected-(LED23-PadC)") (class "Default")
      (node (ref "LED23") (pin "C") (pinfunction "C_C") (pintype "passive"))
    )
    (net (code "191") (name "unconnected-(LED24-PadC)") (class "Default")
      (node (ref "LED24") (pin "C") (pinfunction "C_C") (pintype "passive"))
    )
    (net (code "192") (name "unconnected-(LED25-PadC)") (class "Default")
      (node (ref "LED25") (pin "C") (pinfunction "C_C") (pintype "passive"))
    )
    (net (code "193") (name "unconnected-(LED26-PadC)") (class "Default")
      (node (ref "LED26") (pin "C") (pinfunction "C_C") (pintype "passive"))
    )
    (net (code "194") (name "unconnected-(LED27-PadC)") (class "Default")
      (node (ref "LED27") (pin "C") (pinfunction "C_C") (pintype "passive"))
    )
    (net (code "195") (name "unconnected-(LED28-PadC)") (class "Default")
      (node (ref "LED28") (pin "C") (pinfunction "C_C") (pintype "passive"))
    )
    (net (code "196") (name "unconnected-(LED29-PadC)") (class "Default")
      (node (ref "LED29") (pin "C") (pinfunction "C_C") (pintype "passive"))
    )
    (net (code "197") (name "unconnected-(LED30-PadC)") (class "Default")
      (node (ref "LED30") (pin "C") (pinfunction "C_C") (pintype "passive"))
    )
    (net (code "198") (name "unconnected-(LED31-PadC)") (class "Default")
      (node (ref "LED31") (pin "C") (pinfunction "C_C") (pintype "passive"))
    )
    (net (code "199") (name "unconnected-(LED32-PadC)") (class "Default")
      (node (ref "LED32") (pin "C") (pinfunction "C_C") (pintype "passive"))
    )
    (net (code "200") (name "unconnected-(LED33-PadC)") (class "Default")
      (node (ref "LED33") (pin "C") (pinfunction "C_C") (pintype "passive"))
    )
    (net (code "201") (name "unconnected-(LED34-PadC)") (class "Default")
      (node (ref "LED34") (pin "C") (pinfunction "C_C") (pintype "passive"))
    )
    (net (code "202") (name "unconnected-(LED35-PadC)") (class "Default")
      (node (ref "LED35") (pin "C") (pinfunction "C_C") (pintype "passive"))
    )
    (net (code "203") (name "unconnected-(LED36-PadC)") (class "Default")
      (node (ref "LED36") (pin "C") (pinfunction "C_C") (pintype "passive"))
    )
    (net (code "204") (name "unconnected-(LED37-PadC)") (class "Default")
      (node (ref "LED37") (pin "C") (pinfunction "C_C") (pintype "passive"))
    )
    (net (code "205") (name "unconnected-(LED38-PadC)") (class "Default")
      (node (ref "LED38") (pin "C") (pinfunction "C_C") (pintype "passive"))
    )
    (net (code "206") (name "unconnected-(LED39-PadC)") (class "Default")
      (node (ref "LED39") (pin "C") (pinfunction "C_C") (pintype "passive"))
    )
    (net (code "207") (name "unconnected-(LED40-PadC)") (class "Default")
      (node (ref "LED40") (pin "C") (pinfunction "C_C") (pintype "passive"))
    )
    (net (code "208") (name "unconnected-(LED41-PadC)") (class "Default")
      (node (ref "LED41") (pin "C") (pinfunction "C_C") (pintype "passive"))
    )
    (net (code "209") (name "unconnected-(LED42-PadC)") (class "Default")
      (node (ref "LED42") (pin "C") (pinfunction "C_C") (pintype "passive"))
    )
    (net (code "210") (name "unconnected-(LED43-PadC)") (class "Default")
      (node (ref "LED43") (pin "C") (pinfunction "C_C") (pintype "passive"))
    )
    (net (code "211") (name "unconnected-(LED44-PadC)") (class "Default")
      (node (ref "LED44") (pin "C") (pinfunction "C_C") (pintype "passive"))
    )
    (net (code "212") (name "unconnected-(LED45-PadC)") (class "Default")
      (node (ref "LED45") (pin "C") (pinfunction "C_C") (pintype "passive"))
    )
    (net (code "213") (name "unconnected-(LED46-PadC)") (class "Default")
      (node (ref "LED46") (pin "C") (pinfunction "C_C") (pintype "passive"))
    )
    (net (code "214") (name "unconnected-(LED47-PadC)") (class "Default")
      (node (ref "LED47") (pin "C") (pinfunction "C_C") (pintype "passive"))
    )
    (net (code "215") (name "unconnected-(LED48-PadC)") (class "Default")
      (node (ref "LED48") (pin "C") (pinfunction "C_C") (pintype "passive"))
    )
    (net (code "216") (name "unconnected-(LED49-PadC)") (class "Default")
      (node (ref "LED49") (pin "C") (pinfunction "C_C") (pintype "passive"))
    )
    (net (code "217") (name "unconnected-(LED50-PadC)") (class "Default")
      (node (ref "LED50") (pin "C") (pinfunction "C_C") (pintype "passive"))
    )
    (net (code "218") (name "unconnected-(LED51-PadC)") (class "Default")
      (node (ref "LED51") (pin "C") (pinfunction "C_C") (pintype "passive"))
    )
    (net (code "219") (name "unconnected-(LED52-PadC)") (class "Default")
      (node (ref "LED52") (pin "C") (pinfunction "C_C") (pintype "passive"))
    )
    (net (code "220") (name "unconnected-(LED53-PadC)") (class "Default")
      (node (ref "LED53") (pin "C") (pinfunction "C_C") (pintype "passive"))
    )
    (net (code "221") (name "unconnected-(LED54-PadC)") (class "Default")
      (node (ref "LED54") (pin "C") (pinfunction "C_C") (pintype "passive"))
    )
    (net (code "222") (name "unconnected-(LED55-PadC)") (class "Default")
      (node (ref "LED55") (pin "C") (pinfunction "C_C") (pintype "passive"))
    )
    (net (code "223") (name "unconnected-(LED56-PadC)") (class "Default")
      (node (ref "LED56") (pin "C") (pinfunction "C_C") (pintype "passive"))
    )
    (net (code "224") (name "unconnected-(LED57-PadC)") (class "Default")
      (node (ref "LED57") (pin "C") (pinfunction "C_C") (pintype "passive"))
    )
    (net (code "225") (name "unconnected-(LED58-PadC)") (class "Default")
      (node (ref "LED58") (pin "C") (pinfunction "C_C") (pintype "passive"))
    )
    (net (code "226") (name "unconnected-(LED59-PadC)") (class "Default")
      (node (ref "LED59") (pin "C") (pinfunction "C_C") (pintype "passive"))
    )
    (net (code "227") (name "unconnected-(LED60-PadC)") (class "Default")
      (node (ref "LED60") (pin "C") (pinfunction "C_C") (pintype "passive"))
    )
    (net (code "228") (name "unconnected-(LED61-PadC)") (class "Default")
      (node (ref "LED61") (pin "C") (pinfunction "C_C") (pintype "passive"))
    )
    (net (code "229") (name "unconnected-(LED62-PadC)") (class "Default")
      (node (ref "LED62") (pin "C") (pinfunction "C_C") (pintype "passive"))
    )
    (net (code "230") (name "unconnected-(LED63-PadC)") (class "Default")
      (node (ref "LED63") (pin "C") (pinfunction "C_C") (pintype "passive"))
    )
    (net (code "231") (name "unconnected-(LED64-PadC)") (class "Default")
      (node (ref "LED64") (pin "C") (pinfunction "C_C") (pintype "passive"))
    )
    (net (code "232") (name "unconnected-(LED65-PadC)") (class "Default")
      (node (ref "LED65") (pin "C") (pinfunction "C_C") (pintype "passive"))
    )
    (net (code "233") (name "unconnected-(LED66-PadC)") (class "Default")
      (node (ref "LED66") (pin "C") (pinfunction "C_C") (pintype "passive"))
    )
    (net (code "234") (name "unconnected-(LED67-PadC)") (class "Default")
      (node (ref "LED67") (pin "C") (pinfunction "C_C") (pintype "passive"))
    )
    (net (code "235") (name "unconnected-(LED68-PadC)") (class "Default")
      (node (ref "LED68") (pin "C") (pinfunction "C_C") (pintype "passive"))
    )
    (net (code "236") (name "unconnected-(LED69-PadC)") (class "Default")
      (node (ref "LED69") (pin "C") (pinfunction "C_C") (pintype "passive"))
    )
    (net (code "237") (name "unconnected-(LED70-PadC)") (class "Default")
      (node (ref "LED70") (pin "C") (pinfunction "C_C") (pintype "passive"))
    )
    (net (code "238") (name "unconnected-(LED71-PadC)") (class "Default")
      (node (ref "LED71") (pin "C") (pinfunction "C_C") (pintype "passive"))
    )
    (net (code "239") (name "unconnected-(LED72-PadC)") (class "Default")
      (node (ref "LED72") (pin "C") (pinfunction "C_C") (pintype "passive"))
    )
    (net (code "240") (name "unconnected-(LED73-PadC)") (class "Default")
      (node (ref "LED73") (pin "C") (pinfunction "C_C") (pintype "passive"))
    )
    (net (code "241") (name "unconnected-(LED74-PadC)") (class "Default")
      (node (ref "LED74") (pin "C") (pinfunction "C_C") (pintype "passive"))
    )
    (net (code "242") (name "unconnected-(LED75-PadC)") (class "Default")
      (node (ref "LED75") (pin "C") (pinfunction "C_C") (pintype "passive"))
    )
    (net (code "243") (name "unconnected-(LED76-PadC)") (class "Default")
      (node (ref "LED76") (pin "C") (pinfunction "C_C") (pintype "passive"))
    )
    (net (code "244") (name "unconnected-(LED77-PadC)") (class "Default")
      (node (ref "LED77") (pin "C") (pinfunction "C_C") (pintype "passive"))
    )
    (net (code "245") (name "unconnected-(LED78-PadC)") (class "Default")
      (node (ref "LED78") (pin "C") (pinfunction "C_C") (pintype "passive"))
    )
    (net (code "246") (name "unconnected-(LED79-PadC)") (class "Default")
      (node (ref "LED79") (pin "C") (pinfunction "C_C") (pintype "passive"))
    )
    (net (code "247") (name "unconnected-(LED80-PadC)") (class "Default")
      (node (ref "LED80") (pin "C") (pinfunction "C_C") (pintype "passive"))
    )
    (net (code "248") (name "unconnected-(LED81-PadC)") (class "Default")
      (node (ref "LED81") (pin "C") (pinfunction "C_C") (pintype "passive"))
    )
    (net (code "249") (name "unconnected-(LED82-PadC)") (class "Default")
      (node (ref "LED82") (pin "C") (pinfunction "C_C") (pintype "passive"))
    )
    (net (code "250") (name "unconnected-(LED83-PadC)") (class "Default")
      (node (ref "LED83") (pin "C") (pinfunction "C_C") (pintype "passive"))
    )
    (net (code "251") (name "unconnected-(LED84-PadC)") (class "Default")
      (node (ref "LED84") (pin "C") (pinfunction "C_C") (pintype "passive"))
    )
    (net (code "252") (name "unconnected-(LED85-PadC)") (class "Default")
      (node (ref "LED85") (pin "C") (pinfunction "C_C") (pintype "passive"))
    )
    (net (code "253") (name "unconnected-(LED86-PadC)") (class "Default")
      (node (ref "LED86") (pin "C") (pinfunction "C_C") (pintype "passive"))
    )
    (net (code "254") (name "unconnected-(LED87-PadC)") (class "Default")
      (node (ref "LED87") (pin "C") (pinfunction "C_C") (pintype "passive"))
    )
    (net (code "255") (name "unconnected-(LED88-PadC)") (class "Default")
      (node (ref "LED88") (pin "C") (pinfunction "C_C") (pintype "passive"))
    )
    (net (code "256") (name "unconnected-(LED89-PadC)") (class "Default")
      (node (ref "LED89") (pin "C") (pinfunction "C_C") (pintype "passive"))
    )
    (net (code "257") (name "unconnected-(LED90-PadC)") (class "Default")
      (node (ref "LED90") (pin "C") (pinfunction "C_C") (pintype "passive"))
    )
    (net (code "258") (name "unconnected-(LED91-PadC)") (class "Default")
      (node (ref "LED91") (pin "C") (pinfunction "C_C") (pintype "passive"))
    )
    (net (code "259") (name "unconnected-(LED92-PadC)") (class "Default")
      (node (ref "LED92") (pin "C") (pinfunction "C_C") (pintype "passive"))
    )
    (net (code "260") (name "unconnected-(LED93-PadC)") (class "Default")
      (node (ref "LED93") (pin "C") (pinfunction "C_C") (pintype "passive"))
    )
    (net (code "261") (name "unconnected-(LED94-PadC)") (class "Default")
      (node (ref "LED94") (pin "C") (pinfunction "C_C") (pintype "passive"))
    )
    (net (code "262") (name "unconnected-(LED95-PadC)") (class "Default")
      (node (ref "LED95") (pin "C") (pinfunction "C_C") (pintype "passive"))
    )
    (net (code "263") (name "unconnected-(LED96-PadC)") (class "Default")
      (node (ref "LED96") (pin "C") (pinfunction "C_C") (pintype "passive"))
    )
    (net (code "264") (name "unconnected-(LED97-PadC)") (class "Default")
      (node (ref "LED97") (pin "C") (pinfunction "C_C") (pintype "passive"))
    )
    (net (code "265") (name "unconnected-(LED98-PadC)") (class "Default")
      (node (ref "LED98") (pin "C") (pinfunction "C_C") (pintype "passive"))
    )
    (net (code "266") (name "unconnected-(LED99-PadC)") (class "Default")
      (node (ref "LED99") (pin "C") (pinfunction "C_C") (pintype "passive"))
    )
    (net (code "267") (name "unconnected-(LED100-PadC)") (class "Default")
      (node (ref "LED100") (pin "C") (pinfunction "C_C") (pintype "passive"))
    )
    (net (code "268") (name "unconnected-(LED101-PadC)") (class "Default")
      (node (ref "LED101") (pin "C") (pinfunction "C_C") (pintype "passive"))
    )
    (net (code "269") (name "unconnected-(LED102-PadC)") (class "Default")
      (node (ref "LED102") (pin "C") (pinfunction "C_C") (pintype "passive"))
    )
    (net (code "270") (name "unconnected-(LED103-PadC)") (class "Default")
      (node (ref "LED103") (pin "C") (pinfunction "C_C") (pintype "passive"))
    )
    (net (code "271") (name "unconnected-(LED104-PadC)") (class "Default")
      (node (ref "LED104") (pin "C") (pinfunction "C_C") (pintype "passive"))
    )
    (net (code "272") (name "unconnected-(LED105-PadC)") (class "Default")
      (node (ref "LED105") (pin "C") (pinfunction "C_C") (pintype "passive"))
    )
    (net (code "273") (name "unconnected-(LED106-PadC)") (class "Default")
      (node (ref "LED106") (pin "C") (pinfunction "C_C") (pintype "passive"))
    )
    (net (code "274") (name "unconnected-(LED107-PadC)") (class "Default")
      (node (ref "LED107") (pin "C") (pinfunction "C_C") (pintype "passive"))
    )
    (net (code "275") (name "unconnected-(LED108-PadC)") (class "Default")
      (node (ref "LED108") (pin "C") (pinfunction "C_C") (pintype "passive"))
    )
    (net (code "276") (name "unconnected-(LED109-PadC)") (class "Default")
      (node (ref "LED109") (pin "C") (pinfunction "C_C") (pintype "passive"))
    )
    (net (code "277") (name "unconnected-(LED110-PadC)") (class "Default")
      (node (ref "LED110") (pin "C") (pinfunction "C_C") (pintype "passive"))
    )
    (net (code "278") (name "unconnected-(LED111-PadC)") (class "Default")
      (node (ref "LED111") (pin "C") (pinfunction "C_C") (pintype "passive"))
    )
    (net (code "279") (name "unconnected-(LED112-PadC)") (class "Default")
      (node (ref "LED112") (pin "C") (pinfunction "C_C") (pintype "passive"))
    )
    (net (code "280") (name "unconnected-(LED113-PadC)") (class "Default")
      (node (ref "LED113") (pin "C") (pinfunction "C_C") (pintype "passive"))
    )
    (net (code "281") (name "unconnected-(LED114-PadC)") (class "Default")
      (node (ref "LED114") (pin "C") (pinfunction "C_C") (pintype "passive"))
    )
    (net (code "282") (name "unconnected-(LED115-PadC)") (class "Default")
      (node (ref "LED115") (pin "C") (pinfunction "C_C") (pintype "passive"))
    )
    (net (code "283") (name "unconnected-(LED116-PadC)") (class "Default")
      (node (ref "LED116") (pin "C") (pinfunction "C_C") (pintype "passive"))
    )
    (net (code "284") (name "unconnected-(LED117-PadC)") (class "Default")
      (node (ref "LED117") (pin "C") (pinfunction "C_C") (pintype "passive"))
    )
    (net (code "285") (name "unconnected-(LED118-PadC)") (class "Default")
      (node (ref "LED118") (pin "C") (pinfunction "C_C") (pintype "passive"))
    )
    (net (code "286") (name "unconnected-(LED119-PadC)") (class "Default")
      (node (ref "LED119") (pin "C") (pinfunction "C_C") (pintype "passive"))
    )
    (net (code "287") (name "unconnected-(LED120-PadC)") (class "Default")
      (node (ref "LED120") (pin "C") (pinfunction "C_C") (pintype "passive"))
    )
    (net (code "288") (name "unconnected-(LED121-PadC)") (class "Default")
      (node (ref "LED121") (pin "C") (pinfunction "C_C") (pintype "passive"))
    )
    (net (code "289") (name "unconnected-(LED122-PadC)") (class "Default")
      (node (ref "LED122") (pin "C") (pinfunction "C_C") (pintype "passive"))
    )
    (net (code "290") (name "unconnected-(LED123-PadC)") (class "Default")
      (node (ref "LED123") (pin "C") (pinfunction "C_C") (pintype "passive"))
    )
    (net (code "291") (name "unconnected-(LED124-PadC)") (class "Default")
      (node (ref "LED124") (pin "C") (pinfunction "C_C") (pintype "passive"))
    )
    (net (code "292") (name "unconnected-(LED125-PadC)") (class "Default")
      (node (ref "LED125") (pin "C") (pinfunction "C_C") (pintype "passive"))
    )
    (net (code "293") (name "unconnected-(LED126-PadC)") (class "Default")
      (node (ref "LED126") (pin "C") (pinfunction "C_C") (pintype "passive"))
    )
    (net (code "294") (name "unconnected-(LED127-PadC)") (class "Default")
      (node (ref "LED127") (pin "C") (pinfunction "C_C") (pintype "passive"))
    )
    (net (code "295") (name "unconnected-(LED128-PadC)") (class "Default")
      (node (ref "LED128") (pin "C") (pinfunction "C_C") (pintype "passive"))
    )
    (net (code "296") (name "unconnected-(LED129-PadC)") (class "Default")
      (node (ref "LED129") (pin "C") (pinfunction "C_C") (pintype "passive"))
    )
    (net (code "297") (name "unconnected-(LED130-PadC)") (class "Default")
      (node (ref "LED130") (pin "C") (pinfunction "C_C") (pintype "passive"))
    )
    (net (code "298") (name "unconnected-(LED131-PadC)") (class "Default")
      (node (ref "LED131") (pin "C") (pinfunction "C_C") (pintype "passive"))
    )
    (net (code "299") (name "unconnected-(LED132-PadC)") (class "Default")
      (node (ref "LED132") (pin "C") (pinfunction "C_C") (pintype "passive"))
    )
    (net (code "300") (name "unconnected-(LED133-PadC)") (class "Default")
      (node (ref "LED133") (pin "C") (pinfunction "C_C") (pintype "passive"))
    )
    (net (code "301") (name "unconnected-(LED134-PadC)") (class "Default")
      (node (ref "LED134") (pin "C") (pinfunction "C_C") (pintype "passive"))
    )
    (net (code "302") (name "unconnected-(LED135-PadC)") (class "Default")
      (node (ref "LED135") (pin "C") (pinfunction "C_C") (pintype "passive"))
    )
    (net (code "303") (name "unconnected-(LED136-PadC)") (class "Default")
      (node (ref "LED136") (pin "C") (pinfunction "C_C") (pintype "passive"))
    )
    (net (code "304") (name "unconnected-(LED137-PadC)") (class "Default")
      (node (ref "LED137") (pin "C") (pinfunction "C_C") (pintype "passive"))
    )
    (net (code "305") (name "unconnected-(LED138-PadC)") (class "Default")
      (node (ref "LED138") (pin "C") (pinfunction "C_C") (pintype "passive"))
    )
    (net (code "306") (name "unconnected-(U$1-QG-Pad6)") (class "Default")
      (node (ref "U$1") (pin "6") (pinfunction "QG_6") (pintype "bidirectional"))
    )
    (net (code "307") (name "unconnected-(U$1-QH*-Pad9)") (class "Default")
      (node (ref "U$1") (pin "9") (pinfunction "QH*_9") (pintype "bidirectional"))
    )
    (net (code "308") (name "unconnected-(U$1-QH-Pad7)") (class "Default")
      (node (ref "U$1") (pin "7") (pinfunction "QH_7") (pintype "bidirectional"))
    )
    (net (code "309") (name "unconnected-(U$2-QG-Pad6)") (class "Default")
      (node (ref "U$2") (pin "6") (pinfunction "QG_6") (pintype "bidirectional"))
    )
    (net (code "310") (name "unconnected-(U$2-QH*-Pad9)") (class "Default")
      (node (ref "U$2") (pin "9") (pinfunction "QH*_9") (pintype "bidirectional"))
    )
    (net (code "311") (name "unconnected-(U$2-QH-Pad7)") (class "Default")
      (node (ref "U$2") (pin "7") (pinfunction "QH_7") (pintype "bidirectional"))
    )
    (net (code "312") (name "unconnected-(U$3-QG-Pad6)") (class "Default")
      (node (ref "U$3") (pin "6") (pinfunction "QG_6") (pintype "bidirectional"))
    )
    (net (code "313") (name "unconnected-(U$3-QH*-Pad9)") (class "Default")
      (node (ref "U$3") (pin "9") (pinfunction "QH*_9") (pintype "bidirectional"))
    )
    (net (code "314") (name "unconnected-(U$3-QH-Pad7)") (class "Default")
      (node (ref "U$3") (pin "7") (pinfunction "QH_7") (pintype "bidirectional"))
    )
    (net (code "315") (name "unconnected-(U$4-QG-Pad6)") (class "Default")
      (node (ref "U$4") (pin "6") (pinfunction "QG_6") (pintype "bidirectional"))
    )
    (net (code "316") (name "unconnected-(U$4-QH*-Pad9)") (class "Default")
      (node (ref "U$4") (pin "9") (pinfunction "QH*_9") (pintype "bidirectional"))
    )
    (net (code "317") (name "unconnected-(U$4-QH-Pad7)") (class "Default")
      (node (ref "U$4") (pin "7") (pinfunction "QH_7") (pintype "bidirectional"))
    )
    (net (code "318") (name "unconnected-(U$5-QG-Pad6)") (class "Default")
      (node (ref "U$5") (pin "6") (pinfunction "QG_6") (pintype "bidirectional"))
    )
    (net (code "319") (name "unconnected-(U$5-QH*-Pad9)") (class "Default")
      (node (ref "U$5") (pin "9") (pinfunction "QH*_9") (pintype "bidirectional"))
    )
    (net (code "320") (name "unconnected-(U$5-QH-Pad7)") (class "Default")
      (node (ref "U$5") (pin "7") (pinfunction "QH_7") (pintype "bidirectional"))
    )
    (net (code "321") (name "unconnected-(U$6-QG-Pad6)") (class "Default")
      (node (ref "U$6") (pin "6") (pinfunction "QG_6") (pintype "bidirectional"))
    )
    (net (code "322") (name "unconnected-(U$6-QH*-Pad9)") (class "Default")
      (node (ref "U$6") (pin "9") (pinfunction "QH*_9") (pintype "bidirectional"))
    )
    (net (code "323") (name "unconnected-(U$6-QH-Pad7)") (class "Default")
      (node (ref "U$6") (pin "7") (pinfunction "QH_7") (pintype "bidirectional"))
    )
    (net (code "324") (name "unconnected-(U$7-QG-Pad6)") (class "Default")
      (node (ref "U$7") (pin "6") (pinfunction "QG_6") (pintype "bidirectional"))
    )
    (net (code "325") (name "unconnected-(U$7-QH*-Pad9)") (class "Default")
      (node (ref "U$7") (pin "9") (pinfunction "QH*_9") (pintype "bidirectional"))
    )
    (net (code "326") (name "unconnected-(U$7-QH-Pad7)") (class "Default")
      (node (ref "U$7") (pin "7") (pinfunction "QH_7") (pintype "bidirectional"))
    )
    (net (code "327") (name "unconnected-(U$8-QG-Pad6)") (class "Default")
      (node (ref "U$8") (pin "6") (pinfunction "QG_6") (pintype "bidirectional"))
    )
    (net (code "328") (name "unconnected-(U$8-QH*-Pad9)") (class "Default")
      (node (ref "U$8") (pin "9") (pinfunction "QH*_9") (pintype "bidirectional"))
    )
    (net (code "329") (name "unconnected-(U$8-QH-Pad7)") (class "Default")
      (node (ref "U$8") (pin "7") (pinfunction "QH_7") (pintype "bidirectional"))
    )
    (net (code "330") (name "unconnected-(U$9-QG-Pad6)") (class "Default")
      (node (ref "U$9") (pin "6") (pinfunction "QG_6") (pintype "bidirectional"))
    )
    (net (code "331") (name "unconnected-(U$9-QH*-Pad9)") (class "Default")
      (node (ref "U$9") (pin "9") (pinfunction "QH*_9") (pintype "bidirectional"))
    )
    (net (code "332") (name "unconnected-(U$9-QH-Pad7)") (class "Default")
      (node (ref "U$9") (pin "7") (pinfunction "QH_7") (pintype "bidirectional"))
    )
    (net (code "333") (name "unconnected-(U$10-QG-Pad6)") (class "Default")
      (node (ref "U$10") (pin "6") (pinfunction "QG_6") (pintype "bidirectional"))
    )
    (net (code "334") (name "unconnected-(U$10-QH*-Pad9)") (class "Default")
      (node (ref "U$10") (pin "9") (pinfunction "QH*_9") (pintype "bidirectional"))
    )
    (net (code "335") (name "unconnected-(U$10-QH-Pad7)") (class "Default")
      (node (ref "U$10") (pin "7") (pinfunction "QH_7") (pintype "bidirectional"))
    )
    (net (code "336") (name "unconnected-(U$11-QG-Pad6)") (class "Default")
      (node (ref "U$11") (pin "6") (pinfunction "QG_6") (pintype "bidirectional"))
    )
    (net (code "337") (name "unconnected-(U$11-QH*-Pad9)") (class "Default")
      (node (ref "U$11") (pin "9") (pinfunction "QH*_9") (pintype "bidirectional"))
    )
    (net (code "338") (name "unconnected-(U$11-QH-Pad7)") (class "Default")
      (node (ref "U$11") (pin "7") (pinfunction "QH_7") (pintype "bidirectional"))
    )
    (net (code "339") (name "unconnected-(U$12-QG-Pad6)") (class "Default")
      (node (ref "U$12") (pin "6") (pinfunction "QG_6") (pintype "bidirectional"))
    )
    (net (code "340") (name "unconnected-(U$12-QH*-Pad9)") (class "Default")
      (node (ref "U$12") (pin "9") (pinfunction "QH*_9") (pintype "bidirectional"))
    )
    (net (code "341") (name "unconnected-(U$12-QH-Pad7)") (class "Default")
      (node (ref "U$12") (pin "7") (pinfunction "QH_7") (pintype "bidirectional"))
    )
    (net (code "342") (name "unconnected-(U$13-QG-Pad6)") (class "Default")
      (node (ref "U$13") (pin "6") (pinfunction "QG_6") (pintype "bidirectional"))
    )
    (net (code "343") (name "unconnected-(U$13-QH*-Pad9)") (class "Default")
      (node (ref "U$13") (pin "9") (pinfunction "QH*_9") (pintype "bidirectional"))
    )
    (net (code "344") (name "unconnected-(U$13-QH-Pad7)") (class "Default")
      (node (ref "U$13") (pin "7") (pinfunction "QH_7") (pintype "bidirectional"))
    )
    (net (code "345") (name "unconnected-(U$14-QG-Pad6)") (class "Default")
      (node (ref "U$14") (pin "6") (pinfunction "QG_6") (pintype "bidirectional"))
    )
    (net (code "346") (name "unconnected-(U$14-QH*-Pad9)") (class "Default")
      (node (ref "U$14") (pin "9") (pinfunction "QH*_9") (pintype "bidirectional"))
    )
    (net (code "347") (name "unconnected-(U$14-QH-Pad7)") (class "Default")
      (node (ref "U$14") (pin "7") (pinfunction "QH_7") (pintype "bidirectional"))
    )
    (net (code "348") (name "unconnected-(U$15-QG-Pad6)") (class "Default")
      (node (ref "U$15") (pin "6") (pinfunction "QG_6") (pintype "bidirectional"))
    )
    (net (code "349") (name "unconnected-(U$15-QH*-Pad9)") (class "Default")
      (node (ref "U$15") (pin "9") (pinfunction "QH*_9") (pintype "bidirectional"))
    )
    (net (code "350") (name "unconnected-(U$15-QH-Pad7)") (class "Default")
      (node (ref "U$15") (pin "7") (pinfunction "QH_7") (pintype "bidirectional"))
    )
    (net (code "351") (name "unconnected-(U$16-QG-Pad6)") (class "Default")
      (node (ref "U$16") (pin "6") (pinfunction "QG_6") (pintype "bidirectional"))
    )
    (net (code "352") (name "unconnected-(U$16-QH*-Pad9)") (class "Default")
      (node (ref "U$16") (pin "9") (pinfunction "QH*_9") (pintype "bidirectional"))
    )
    (net (code "353") (name "unconnected-(U$16-QH-Pad7)") (class "Default")
      (node (ref "U$16") (pin "7") (pinfunction "QH_7") (pintype "bidirectional"))
    )
    (net (code "354") (name "unconnected-(U$17-QG-Pad6)") (class "Default")
      (node (ref "U$17") (pin "6") (pinfunction "QG_6") (pintype "bidirectional"))
    )
    (net (code "355") (name "unconnected-(U$17-QH*-Pad9)") (class "Default")
      (node (ref "U$17") (pin "9") (pinfunction "QH*_9") (pintype "bidirectional"))
    )
    (net (code "356") (name "unconnected-(U$17-QH-Pad7)") (class "Default")
      (node (ref "U$17") (pin "7") (pinfunction "QH_7") (pintype "bidirectional"))
    )
    (net (code "357") (name "unconnected-(U$18-QG-Pad6)") (class "Default")
      (node (ref "U$18") (pin "6") (pinfunction "QG_6") (pintype "bidirectional"))
    )
    (net (code "358") (name "unconnected-(U$18-QH*-Pad9)") (class "Default")
      (node (ref "U$18") (pin "9") (pinfunction "QH*_9") (pintype "bidirectional"))
    )
    (net (code "359") (name "unconnected-(U$18-QH-Pad7)") (class "Default")
      (node (ref "U$18") (pin "7") (pinfunction "QH_7") (pintype "bidirectional"))
    )
    (net (code "360") (name "unconnected-(U$19-QG-Pad6)") (class "Default")
      (node (ref "U$19") (pin "6") (pinfunction "QG_6") (pintype "bidirectional"))
    )
    (net (code "361") (name "unconnected-(U$19-QH*-Pad9)") (class "Default")
      (node (ref "U$19") (pin "9") (pinfunction "QH*_9") (pintype "bidirectional"))
    )
    (net (code "362") (name "unconnected-(U$19-QH-Pad7)") (class "Default")
      (node (ref "U$19") (pin "7") (pinfunction "QH_7") (pintype "bidirectional"))
    )
    (net (code "363") (name "unconnected-(U$20-QG-Pad6)") (class "Default")
      (node (ref "U$20") (pin "6") (pinfunction "QG_6") (pintype "bidirectional"))
    )
    (net (code "364") (name "unconnected-(U$20-QH*-Pad9)") (class "Default")
      (node (ref "U$20") (pin "9") (pinfunction "QH*_9") (pintype "bidirectional"))
    )
    (net (code "365") (name "unconnected-(U$20-QH-Pad7)") (class "Default")
      (node (ref "U$20") (pin "7") (pinfunction "QH_7") (pintype "bidirectional"))
    )
    (net (code "366") (name "unconnected-(U$21-QG-Pad6)") (class "Default")
      (node (ref "U$21") (pin "6") (pinfunction "QG_6") (pintype "bidirectional"))
    )
    (net (code "367") (name "unconnected-(U$21-QH*-Pad9)") (class "Default")
      (node (ref "U$21") (pin "9") (pinfunction "QH*_9") (pintype "bidirectional"))
    )
    (net (code "368") (name "unconnected-(U$21-QH-Pad7)") (class "Default")
      (node (ref "U$21") (pin "7") (pinfunction "QH_7") (pintype "bidirectional"))
    )
    (net (code "369") (name "unconnected-(U$22-QG-Pad6)") (class "Default")
      (node (ref "U$22") (pin "6") (pinfunction "QG_6") (pintype "bidirectional"))
    )
    (net (code "370") (name "unconnected-(U$22-QH*-Pad9)") (class "Default")
      (node (ref "U$22") (pin "9") (pinfunction "QH*_9") (pintype "bidirectional"))
    )
    (net (code "371") (name "unconnected-(U$22-QH-Pad7)") (class "Default")
      (node (ref "U$22") (pin "7") (pinfunction "QH_7") (pintype "bidirectional"))
    )
    (net (code "372") (name "unconnected-(U$23-QG-Pad6)") (class "Default")
      (node (ref "U$23") (pin "6") (pinfunction "QG_6") (pintype "bidirectional"))
    )
    (net (code "373") (name "unconnected-(U$23-QH*-Pad9)") (class "Default")
      (node (ref "U$23") (pin "9") (pinfunction "QH*_9") (pintype "bidirectional"))
    )
    (net (code "374") (name "unconnected-(U$23-QH-Pad7)") (class "Default")
      (node (ref "U$23") (pin "7") (pinfunction "QH_7") (pintype "bidirectional"))
    )
  )
)
